# BIRDS_X_APRS_v2_7.net
KiCad netlist of a schematic drawn in EAGLE
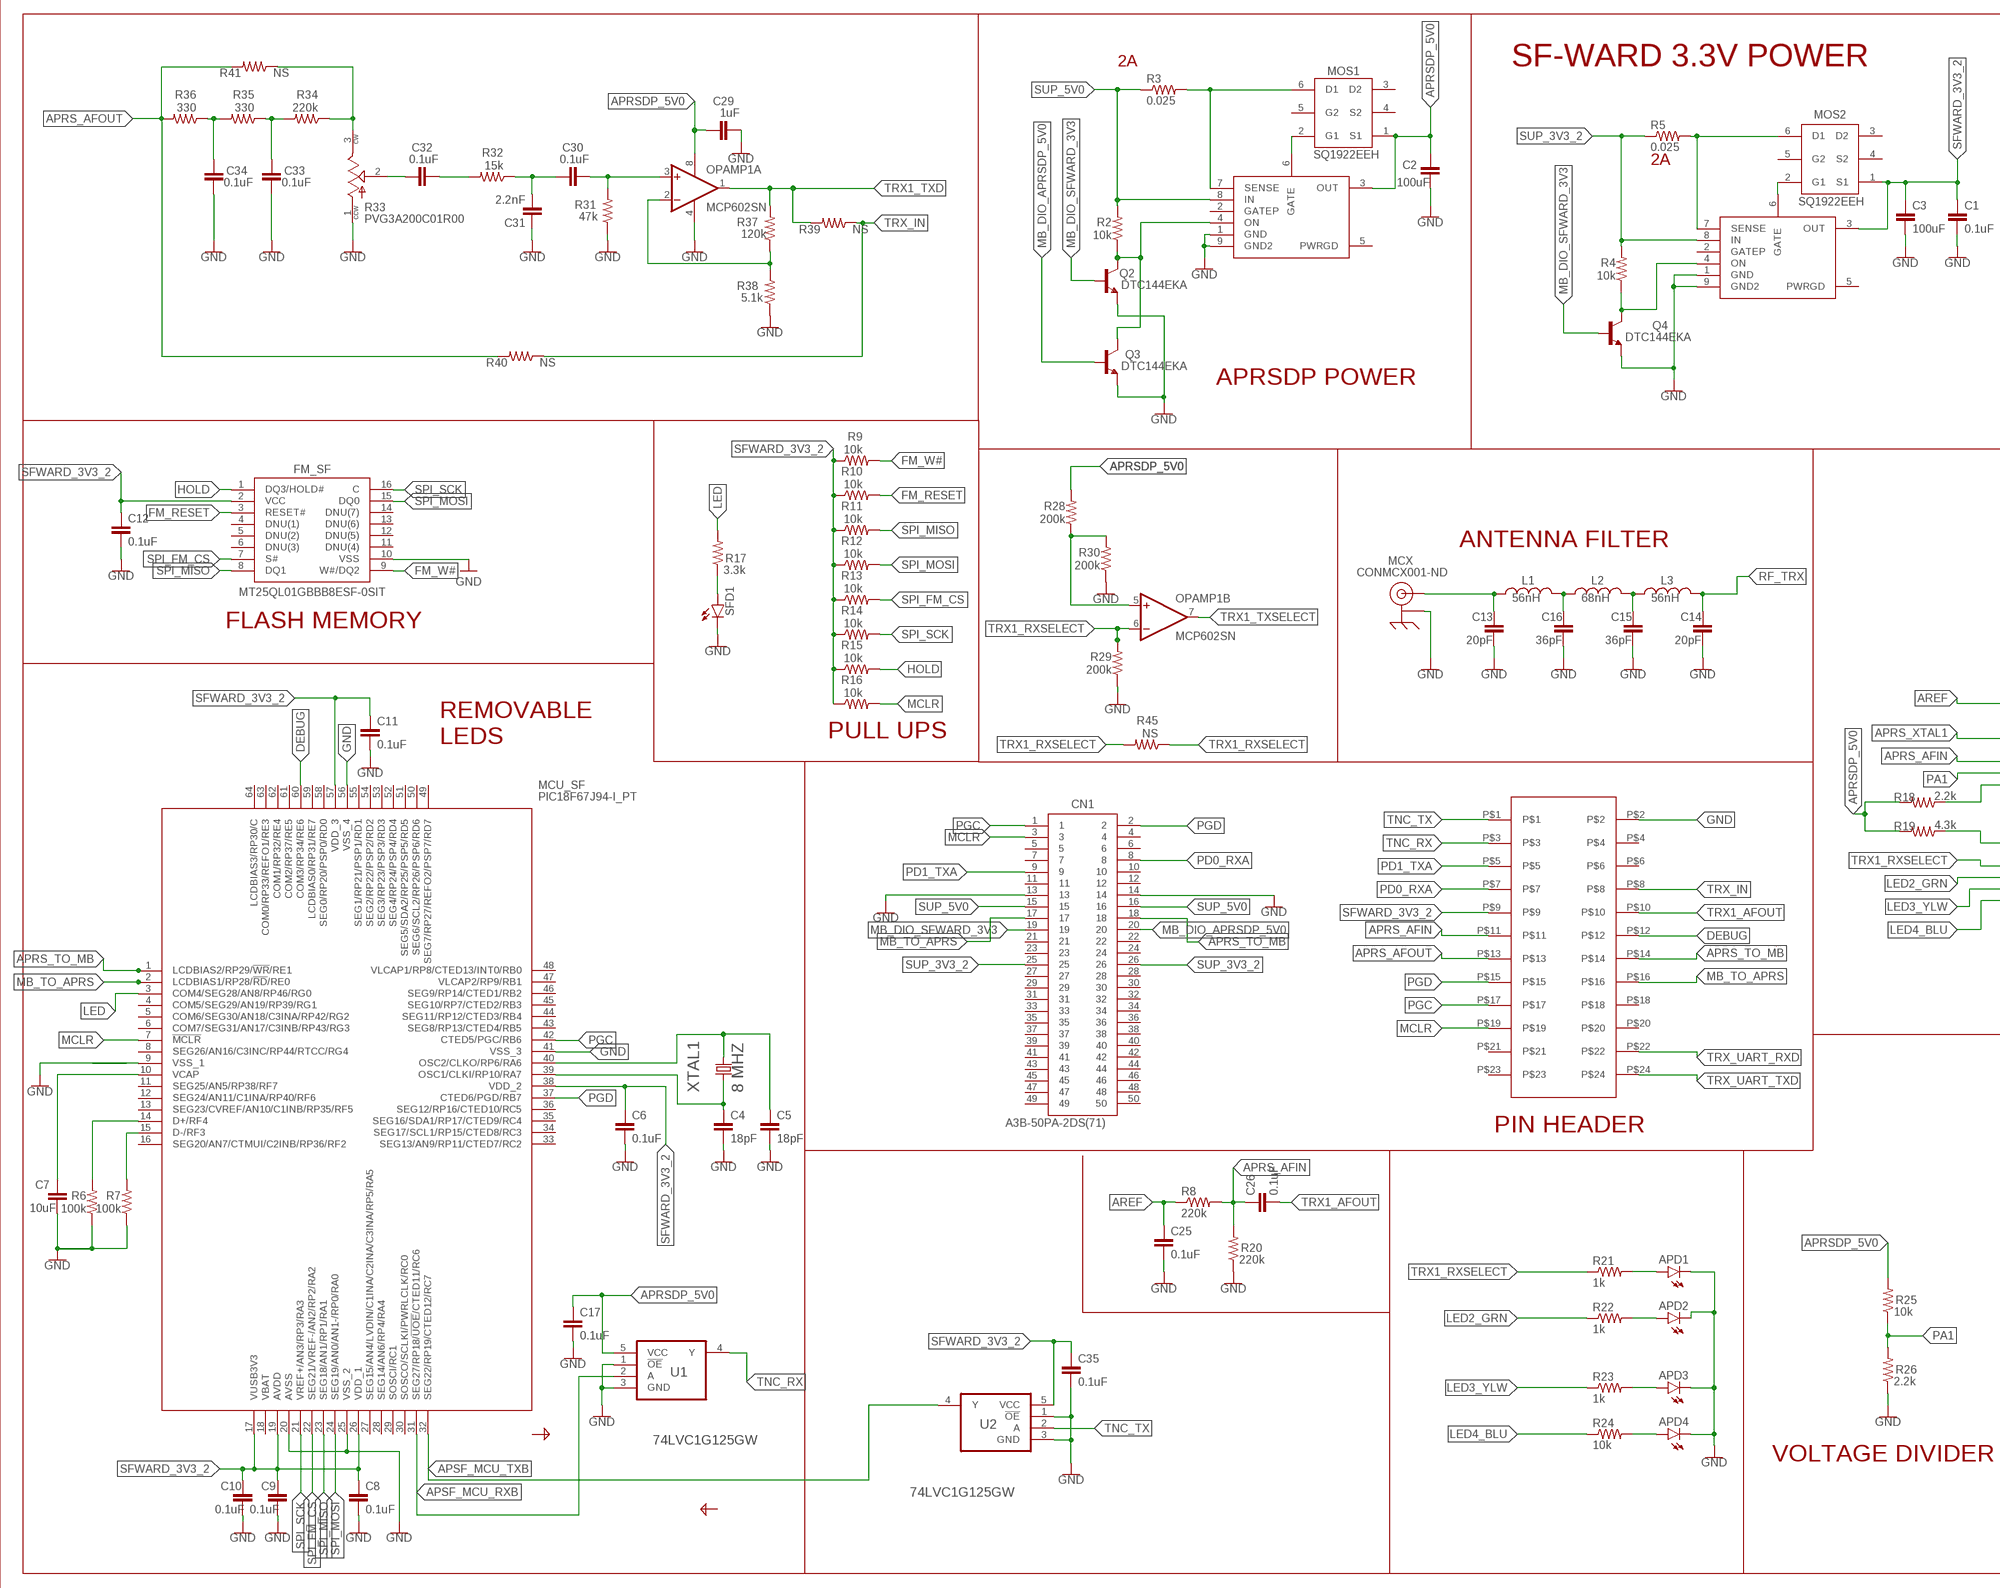
[diagram p0: schematic, sheet 1, part 1 of 2]
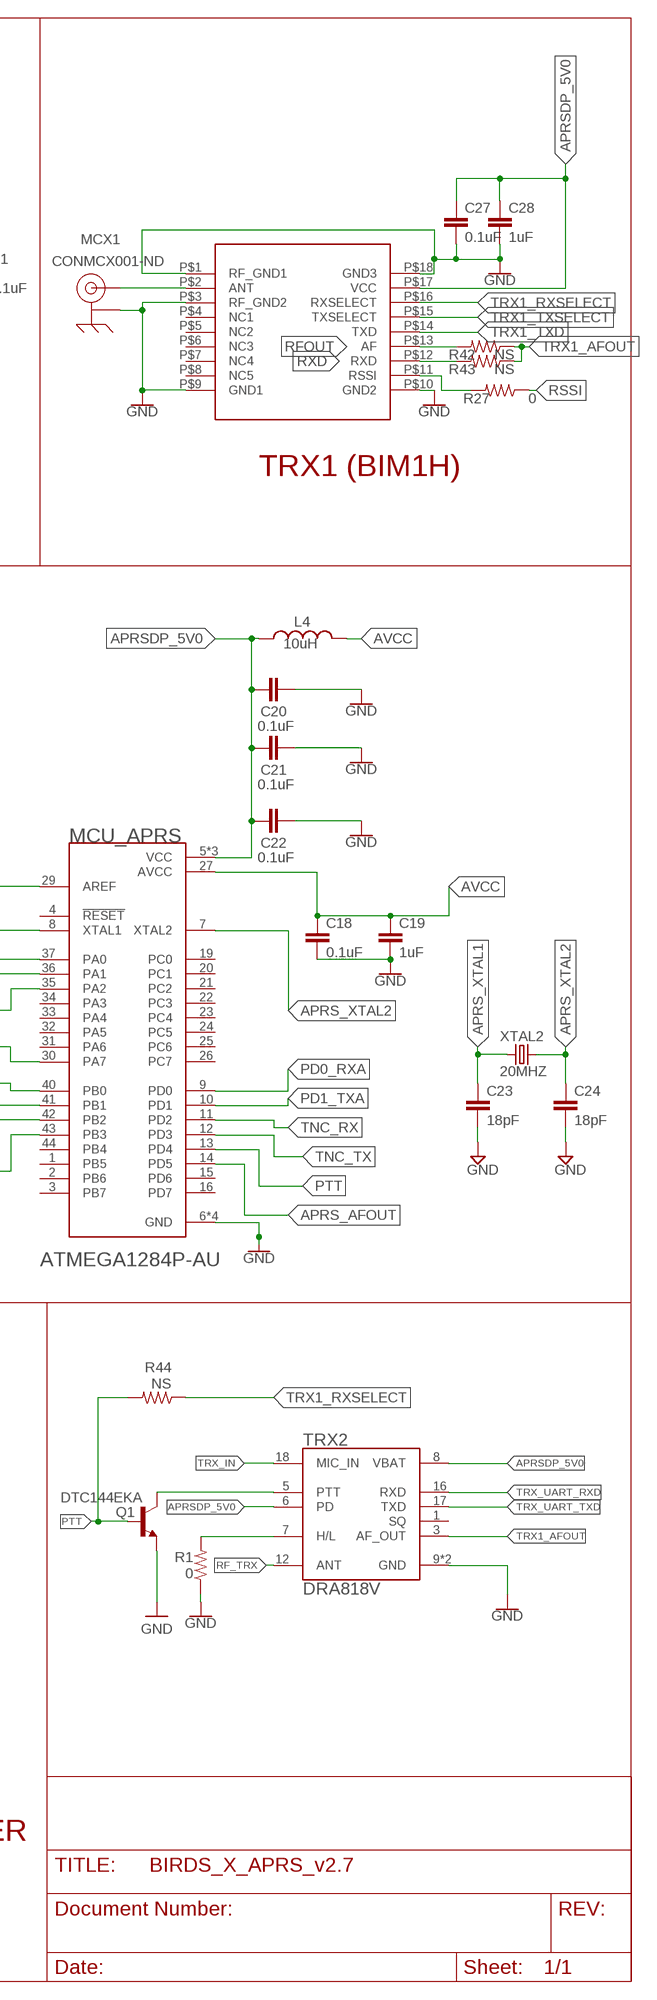
[diagram p1: schematic, sheet 1, part 2 of 2]

(export (version "E")
  (design (tool "Eeschema 10.0.6"))
  (components
    (comp (ref "APD1")
      (value "LEDSML0603")
      (footprint "eagle-import:SML0603")
      (libsource (lib "eagle-import") (part "LEDSML0603"))
    )
    (comp (ref "APD2")
      (value "LEDSML0603")
      (footprint "eagle-import:SML0603")
      (libsource (lib "eagle-import") (part "LEDSML0603"))
    )
    (comp (ref "APD3")
      (value "LEDSML0603")
      (footprint "eagle-import:SML0603")
      (libsource (lib "eagle-import") (part "LEDSML0603"))
    )
    (comp (ref "APD4")
      (value "LEDSML0603")
      (footprint "eagle-import:SML0603")
      (libsource (lib "eagle-import") (part "LEDSML0603"))
    )
    (comp (ref "C1")
      (value "0.1uF")
      (footprint "eagle-import:M(1005)_US(0402)")
      (libsource (lib "eagle-import") (part "CAPACITOR"))
    )
    (comp (ref "C2")
      (value "100uF")
      (footprint "eagle-import:M(2012)_US(0805)")
      (libsource (lib "eagle-import") (part "CAPACITOR2012"))
    )
    (comp (ref "C3")
      (value "100uF")
      (footprint "eagle-import:M(2012)_US(0805)")
      (libsource (lib "eagle-import") (part "CAPACITOR2012"))
    )
    (comp (ref "C4")
      (value "18pF")
      (footprint "eagle-import:M(1005)_US(0402)")
      (libsource (lib "eagle-import") (part "CAPACITOR"))
    )
    (comp (ref "C5")
      (value "18pF")
      (footprint "eagle-import:M(1005)_US(0402)")
      (libsource (lib "eagle-import") (part "CAPACITOR"))
    )
    (comp (ref "C6")
      (value "0.1uF")
      (footprint "eagle-import:M(1005)_US(0402)")
      (libsource (lib "eagle-import") (part "CAPACITOR"))
    )
    (comp (ref "C7")
      (value "10uF")
      (footprint "eagle-import:M(1608)_US(0603)")
      (libsource (lib "eagle-import") (part "CAPACITOR1608"))
    )
    (comp (ref "C8")
      (value "0.1uF")
      (footprint "eagle-import:M(1005)_US(0402)")
      (libsource (lib "eagle-import") (part "CAPACITOR"))
    )
    (comp (ref "C9")
      (value "0.1uF")
      (footprint "eagle-import:M(1005)_US(0402)")
      (libsource (lib "eagle-import") (part "CAPACITOR"))
    )
    (comp (ref "C10")
      (value "0.1uF")
      (footprint "eagle-import:M(1005)_US(0402)")
      (libsource (lib "eagle-import") (part "CAPACITOR"))
    )
    (comp (ref "C11")
      (value "0.1uF")
      (footprint "eagle-import:M(1005)_US(0402)")
      (libsource (lib "eagle-import") (part "CAPACITOR"))
    )
    (comp (ref "C12")
      (value "0.1uF")
      (footprint "eagle-import:M(1005)_US(0402)")
      (libsource (lib "eagle-import") (part "CAPACITOR"))
    )
    (comp (ref "C13")
      (value "20pF")
      (footprint "eagle-import:M(1608)_US(0603)")
      (libsource (lib "eagle-import") (part "CAPACITOR1608"))
    )
    (comp (ref "C14")
      (value "20pF")
      (footprint "eagle-import:M(1608)_US(0603)")
      (libsource (lib "eagle-import") (part "CAPACITOR1608"))
    )
    (comp (ref "C15")
      (value "36pF")
      (footprint "eagle-import:M(1608)_US(0603)")
      (libsource (lib "eagle-import") (part "CAPACITOR1608"))
    )
    (comp (ref "C16")
      (value "36pF")
      (footprint "eagle-import:M(1608)_US(0603)")
      (libsource (lib "eagle-import") (part "CAPACITOR1608"))
    )
    (comp (ref "C17")
      (value "0.1uF")
      (footprint "eagle-import:M(1005)_US(0402)")
      (libsource (lib "eagle-import") (part "CAPACITOR"))
    )
    (comp (ref "C18")
      (value "0.1uF")
      (footprint "eagle-import:M(1005)_US(0402)")
      (libsource (lib "eagle-import") (part "CAPACITOR"))
    )
    (comp (ref "C19")
      (value "1uF")
      (footprint "eagle-import:M(1005)_US(0402)")
      (libsource (lib "eagle-import") (part "CAPACITOR"))
    )
    (comp (ref "C20")
      (value "0.1uF")
      (footprint "eagle-import:M(1005)_US(0402)")
      (libsource (lib "eagle-import") (part "CAPACITOR"))
    )
    (comp (ref "C21")
      (value "0.1uF")
      (footprint "eagle-import:M(1005)_US(0402)")
      (libsource (lib "eagle-import") (part "CAPACITOR"))
    )
    (comp (ref "C22")
      (value "0.1uF")
      (footprint "eagle-import:M(1005)_US(0402)")
      (libsource (lib "eagle-import") (part "CAPACITOR"))
    )
    (comp (ref "C23")
      (value "18pF")
      (footprint "eagle-import:M(1005)_US(0402)")
      (libsource (lib "eagle-import") (part "CAPACITOR"))
    )
    (comp (ref "C24")
      (value "18pF")
      (footprint "eagle-import:M(1005)_US(0402)")
      (libsource (lib "eagle-import") (part "CAPACITOR"))
    )
    (comp (ref "C25")
      (value "0.1uF")
      (footprint "eagle-import:M(1005)_US(0402)")
      (libsource (lib "eagle-import") (part "CAPACITOR"))
    )
    (comp (ref "C26")
      (value "0.1uF")
      (footprint "eagle-import:M(1005)_US(0402)")
      (libsource (lib "eagle-import") (part "CAPACITOR"))
    )
    (comp (ref "C27")
      (value "0.1uF")
      (footprint "eagle-import:M(1005)_US(0402)")
      (libsource (lib "eagle-import") (part "CAPACITOR"))
    )
    (comp (ref "C28")
      (value "1uF")
      (footprint "eagle-import:M(1005)_US(0402)")
      (libsource (lib "eagle-import") (part "CAPACITOR"))
    )
    (comp (ref "C29")
      (value "1uF")
      (footprint "eagle-import:M(1005)_US(0402)")
      (libsource (lib "eagle-import") (part "CAPACITOR"))
    )
    (comp (ref "C30")
      (value "0.1uF")
      (footprint "eagle-import:M(1005)_US(0402)")
      (libsource (lib "eagle-import") (part "CAPACITOR"))
    )
    (comp (ref "C31")
      (value "2.2nF")
      (footprint "eagle-import:M(1005)_US(0402)")
      (libsource (lib "eagle-import") (part "CAPACITOR"))
    )
    (comp (ref "C32")
      (value "0.1uF")
      (footprint "eagle-import:M(1005)_US(0402)")
      (libsource (lib "eagle-import") (part "CAPACITOR"))
    )
    (comp (ref "C33")
      (value "0.1uF")
      (footprint "eagle-import:M(1005)_US(0402)")
      (libsource (lib "eagle-import") (part "CAPACITOR"))
    )
    (comp (ref "C34")
      (value "0.1uF")
      (footprint "eagle-import:M(1005)_US(0402)")
      (libsource (lib "eagle-import") (part "CAPACITOR"))
    )
    (comp (ref "C35")
      (value "0.1uF")
      (footprint "eagle-import:M(1005)_US(0402)")
      (libsource (lib "eagle-import") (part "CAPACITOR"))
    )
    (comp (ref "CN1")
      (value "A3B-50PA-2DS(71)")
      (footprint "eagle-import:A3B-50PA-2DS(71)")
      (libsource (lib "eagle-import") (part "A3B-50PA-2DS(71)"))
    )
    (comp (ref "FM_SF")
      (value "MT25QL01GBBB8ESF-0SIT")
      (footprint "eagle-import:SOIC127P1032X265-16N")
      (libsource (lib "eagle-import") (part "MT25QL01GBBB8ESF-0SIT"))
    )
    (comp (ref "JP1")
      (value "RAB_ACCESS")
      (footprint "eagle-import:RAB_ACCESS")
      (libsource (lib "eagle-import") (part "RAB_ACCESS"))
    )
    (comp (ref "L1")
      (value "56nH")
      (footprint "eagle-import:M(2012)_US(0805)")
      (libsource (lib "eagle-import") (part "INDUCTOR2012"))
    )
    (comp (ref "L2")
      (value "68nH")
      (footprint "eagle-import:M(2012)_US(0805)")
      (libsource (lib "eagle-import") (part "INDUCTOR2012"))
    )
    (comp (ref "L3")
      (value "56nH")
      (footprint "eagle-import:M(2012)_US(0805)")
      (libsource (lib "eagle-import") (part "INDUCTOR2012"))
    )
    (comp (ref "L4")
      (value "10uH")
      (footprint "eagle-import:M(2012)_US(0805)")
      (libsource (lib "eagle-import") (part "INDUCTOR2012"))
    )
    (comp (ref "MCU_APRS")
      (value "ATMEGA1284P-AU")
      (footprint "eagle-import:QFP80P1200X1200X120-44N")
      (fields (field (name "MF") "Microchip"))
      (libsource (lib "eagle-import") (part "ATMEGA1284P-AU"))
    )
    (comp (ref "MCU_SF")
      (value "PIC18F67J94-I_PT")
      (footprint "eagle-import:QFP50P1200X1200X120-64N")
      (fields
        (field (name "MANUFACTURER_PART_NUMBER") "PIC18F67J94-I/PT")
        (field (name "MOUSER_PART_NUMBER") "579-PIC18F67J94-I/PT")
        (field (name "RS_PART_NUMBER") "1652172")
      )
      (libsource (lib "eagle-import") (part "PIC18F67J94-I_PT"))
    )
    (comp (ref "MCX")
      (value "CONMCX001-ND")
      (footprint "eagle-import:CONMCX001-ND")
      (libsource (lib "eagle-import") (part "CONMCX001-ND"))
    )
    (comp (ref "MCX1")
      (value "CONMCX001-ND")
      (footprint "eagle-import:CONMCX001-ND")
      (libsource (lib "eagle-import") (part "CONMCX001-ND"))
    )
    (comp (ref "MOS1")
      (value "SQ1922EEH")
      (footprint "eagle-import:SOT65P210X110-6N")
      (libsource (lib "eagle-import") (part "SQ1922EEH"))
    )
    (comp (ref "MOS2")
      (value "SQ1922EEH")
      (footprint "eagle-import:SOT65P210X110-6N")
      (libsource (lib "eagle-import") (part "SQ1922EEH"))
    )
    (comp (ref "OCP1")
      (value "BIRDS5_LTC4361")
      (footprint "eagle-import:BIRDS5_LTC4361")
      (libsource (lib "eagle-import") (part "BIRDS5_LTC4361"))
    )
    (comp (ref "OCP2")
      (value "BIRDS5_LTC4361")
      (footprint "eagle-import:BIRDS5_LTC4361")
      (libsource (lib "eagle-import") (part "BIRDS5_LTC4361"))
    )
    (comp (ref "OPAMP1")
      (value "MCP602SN")
      (footprint "eagle-import:SO08")
      (libsource (lib "eagle-import") (part "MCP602SN"))
    )
    (comp (ref "Q1")
      (value "DTC144EKA")
      (footprint "eagle-import:SOT346-R")
      (libsource (lib "eagle-import") (part "DTC144EKA"))
    )
    (comp (ref "Q2")
      (value "DTC144EKA")
      (footprint "eagle-import:SOT346-R")
      (libsource (lib "eagle-import") (part "DTC144EKA"))
    )
    (comp (ref "Q3")
      (value "DTC144EKA")
      (footprint "eagle-import:SOT346-R")
      (libsource (lib "eagle-import") (part "DTC144EKA"))
    )
    (comp (ref "Q4")
      (value "DTC144EKA")
      (footprint "eagle-import:SOT346-R")
      (libsource (lib "eagle-import") (part "DTC144EKA"))
    )
    (comp (ref "R1")
      (value "0")
      (footprint "eagle-import:M(1005)_US(0402)")
      (libsource (lib "eagle-import") (part "RESISTOR"))
    )
    (comp (ref "R2")
      (value "10k")
      (footprint "eagle-import:M(1005)_US(0402)")
      (libsource (lib "eagle-import") (part "RESISTOR"))
    )
    (comp (ref "R3")
      (value "0.025")
      (footprint "eagle-import:M(2012)_US(0805)")
      (libsource (lib "eagle-import") (part "RESISTOR2012"))
    )
    (comp (ref "R4")
      (value "10k")
      (footprint "eagle-import:M(1005)_US(0402)")
      (libsource (lib "eagle-import") (part "RESISTOR"))
    )
    (comp (ref "R5")
      (value "0.025")
      (footprint "eagle-import:M(2012)_US(0805)")
      (libsource (lib "eagle-import") (part "RESISTOR2012"))
    )
    (comp (ref "R6")
      (value "100k")
      (footprint "eagle-import:M(1005)_US(0402)")
      (libsource (lib "eagle-import") (part "RESISTOR"))
    )
    (comp (ref "R7")
      (value "100k")
      (footprint "eagle-import:M(1005)_US(0402)")
      (libsource (lib "eagle-import") (part "RESISTOR"))
    )
    (comp (ref "R8")
      (value "220k")
      (footprint "eagle-import:M(1608)_US(0603)")
      (libsource (lib "eagle-import") (part "RESISTOR1608"))
    )
    (comp (ref "R9")
      (value "10k")
      (footprint "eagle-import:M(1005)_US(0402)")
      (libsource (lib "eagle-import") (part "RESISTOR"))
    )
    (comp (ref "R10")
      (value "10k")
      (footprint "eagle-import:M(1005)_US(0402)")
      (libsource (lib "eagle-import") (part "RESISTOR"))
    )
    (comp (ref "R11")
      (value "10k")
      (footprint "eagle-import:M(1005)_US(0402)")
      (libsource (lib "eagle-import") (part "RESISTOR"))
    )
    (comp (ref "R12")
      (value "10k")
      (footprint "eagle-import:M(1005)_US(0402)")
      (libsource (lib "eagle-import") (part "RESISTOR"))
    )
    (comp (ref "R13")
      (value "10k")
      (footprint "eagle-import:M(1005)_US(0402)")
      (libsource (lib "eagle-import") (part "RESISTOR"))
    )
    (comp (ref "R14")
      (value "10k")
      (footprint "eagle-import:M(1005)_US(0402)")
      (libsource (lib "eagle-import") (part "RESISTOR"))
    )
    (comp (ref "R15")
      (value "10k")
      (footprint "eagle-import:M(1005)_US(0402)")
      (libsource (lib "eagle-import") (part "RESISTOR"))
    )
    (comp (ref "R16")
      (value "10k")
      (footprint "eagle-import:M(1005)_US(0402)")
      (libsource (lib "eagle-import") (part "RESISTOR"))
    )
    (comp (ref "R17")
      (value "3.3k")
      (footprint "eagle-import:M(1608)_US(0603)")
      (libsource (lib "eagle-import") (part "RESISTOR1608"))
    )
    (comp (ref "R18")
      (value "2.2k")
      (footprint "eagle-import:M(1005)_US(0402)")
      (libsource (lib "eagle-import") (part "RESISTOR"))
    )
    (comp (ref "R19")
      (value "4.3k")
      (footprint "eagle-import:M(1005)_US(0402)")
      (libsource (lib "eagle-import") (part "RESISTOR"))
    )
    (comp (ref "R20")
      (value "220k")
      (footprint "eagle-import:M(1608)_US(0603)")
      (libsource (lib "eagle-import") (part "RESISTOR1608"))
    )
    (comp (ref "R21")
      (value "1k")
      (footprint "eagle-import:M(1608)_US(0603)")
      (libsource (lib "eagle-import") (part "RESISTOR1608"))
    )
    (comp (ref "R22")
      (value "1k")
      (footprint "eagle-import:M(1608)_US(0603)")
      (libsource (lib "eagle-import") (part "RESISTOR1608"))
    )
    (comp (ref "R23")
      (value "1k")
      (footprint "eagle-import:M(1608)_US(0603)")
      (libsource (lib "eagle-import") (part "RESISTOR1608"))
    )
    (comp (ref "R24")
      (value "10k")
      (footprint "eagle-import:M(1608)_US(0603)")
      (libsource (lib "eagle-import") (part "RESISTOR1608"))
    )
    (comp (ref "R25")
      (value "10k")
      (footprint "eagle-import:M(1608)_US(0603)")
      (libsource (lib "eagle-import") (part "RESISTOR1608"))
    )
    (comp (ref "R26")
      (value "2.2k")
      (footprint "eagle-import:M(1608)_US(0603)")
      (libsource (lib "eagle-import") (part "RESISTOR1608"))
    )
    (comp (ref "R27")
      (value "0")
      (footprint "eagle-import:M(1608)_US(0603)")
      (libsource (lib "eagle-import") (part "RESISTOR1608"))
    )
    (comp (ref "R28")
      (value "200k")
      (footprint "eagle-import:M(1005)_US(0402)")
      (libsource (lib "eagle-import") (part "RESISTOR"))
    )
    (comp (ref "R29")
      (value "200k")
      (footprint "eagle-import:M(1005)_US(0402)")
      (libsource (lib "eagle-import") (part "RESISTOR"))
    )
    (comp (ref "R30")
      (value "200k")
      (footprint "eagle-import:M(1005)_US(0402)")
      (libsource (lib "eagle-import") (part "RESISTOR"))
    )
    (comp (ref "R31")
      (value "47k")
      (footprint "eagle-import:M(1608)_US(0603)")
      (libsource (lib "eagle-import") (part "RESISTOR1608"))
    )
    (comp (ref "R32")
      (value "15k")
      (footprint "eagle-import:M(1608)_US(0603)")
      (libsource (lib "eagle-import") (part "RESISTOR1608"))
    )
    (comp (ref "R33")
      (value "PVG3A200C01R00")
      (footprint "eagle-import:TRIM_PVG3A200C01R00")
      (fields (field (name "DIGI-KEY_PART_NUMBER") "490-2647-1-ND") (field (name "MF") "Bourns"))
      (libsource (lib "eagle-import") (part "PVG3A200C01R00"))
    )
    (comp (ref "R34")
      (value "220k")
      (footprint "eagle-import:M(1608)_US(0603)")
      (libsource (lib "eagle-import") (part "RESISTOR1608"))
    )
    (comp (ref "R35")
      (value "330")
      (footprint "eagle-import:M(1608)_US(0603)")
      (libsource (lib "eagle-import") (part "RESISTOR1608"))
    )
    (comp (ref "R36")
      (value "330")
      (footprint "eagle-import:M(1608)_US(0603)")
      (libsource (lib "eagle-import") (part "RESISTOR1608"))
    )
    (comp (ref "R37")
      (value "120k")
      (footprint "eagle-import:M(1608)_US(0603)")
      (libsource (lib "eagle-import") (part "RESISTOR1608"))
    )
    (comp (ref "R38")
      (value "5.1k")
      (footprint "eagle-import:M(1608)_US(0603)")
      (libsource (lib "eagle-import") (part "RESISTOR1608"))
    )
    (comp (ref "R39")
      (value "NS")
      (footprint "eagle-import:M(1608)_US(0603)")
      (libsource (lib "eagle-import") (part "RESISTOR1608"))
    )
    (comp (ref "R40")
      (value "NS")
      (footprint "eagle-import:M(1608)_US(0603)")
      (libsource (lib "eagle-import") (part "RESISTOR1608"))
    )
    (comp (ref "R41")
      (value "NS")
      (footprint "eagle-import:M(1608)_US(0603)")
      (libsource (lib "eagle-import") (part "RESISTOR1608"))
    )
    (comp (ref "R42")
      (value "NS")
      (footprint "eagle-import:M(1608)_US(0603)")
      (libsource (lib "eagle-import") (part "RESISTOR1608"))
    )
    (comp (ref "R43")
      (value "NS")
      (footprint "eagle-import:M(1608)_US(0603)")
      (libsource (lib "eagle-import") (part "RESISTOR1608"))
    )
    (comp (ref "R44")
      (value "NS")
      (footprint "eagle-import:M(1608)_US(0603)")
      (libsource (lib "eagle-import") (part "RESISTOR1608"))
    )
    (comp (ref "R45")
      (value "NS")
      (footprint "eagle-import:M(1608)_US(0603)")
      (libsource (lib "eagle-import") (part "RESISTOR1608"))
    )
    (comp (ref "SFD1")
      (value "LEDCHIPLED_0603")
      (footprint "eagle-import:CHIPLED_0603")
      (libsource (lib "eagle-import") (part "LEDCHIPLED_0603"))
    )
    (comp (ref "TRX1")
      (value "BIM1H")
      (footprint "eagle-import:BIM1H")
      (libsource (lib "eagle-import") (part "BIM1H"))
    )
    (comp (ref "TRX2")
      (value "DRA818V")
      (footprint "eagle-import:DORJI_DRA818V")
      (fields (field (name "MF") "DORJI"))
      (libsource (lib "eagle-import") (part "DRA818V"))
    )
    (comp (ref "U1")
      (value "74LVC1G125GW")
      (footprint "eagle-import:SOT65P210X110-5N")
      (fields (field (name "MF") "NXP Semiconductors"))
      (libsource (lib "eagle-import") (part "74LVC1G125GW"))
    )
    (comp (ref "U2")
      (value "74LVC1G125GW")
      (footprint "eagle-import:SOT65P210X110-5N")
      (fields (field (name "MF") "NXP Semiconductors"))
      (libsource (lib "eagle-import") (part "74LVC1G125GW"))
    )
    (comp (ref "XTAL1")
      (value "8 MHZ")
      (footprint "eagle-import:CRYSTAL_SM49")
      (libsource (lib "eagle-import") (part "CRYSTAL_CRYSTALSM49"))
    )
    (comp (ref "XTAL2")
      (value "20MHZ")
      (footprint "eagle-import:SM49")
      (libsource (lib "eagle-import") (part "CRYSTALSM49"))
    )
  )
  (nets
    (net (code "1") (name "APRSDP_5V0") (class "Default")
      (node (ref "C17") (pin "1") (pinfunction "1_1") (pintype "passive"))
      (node (ref "C2") (pin "1") (pinfunction "1_1") (pintype "passive"))
      (node (ref "C20") (pin "1") (pinfunction "1_1") (pintype "passive"))
      (node (ref "C21") (pin "1") (pinfunction "1_1") (pintype "passive"))
      (node (ref "C22") (pin "1") (pinfunction "1_1") (pintype "passive"))
      (node (ref "C27") (pin "1") (pinfunction "1_1") (pintype "passive"))
      (node (ref "C28") (pin "1") (pinfunction "1_1") (pintype "passive"))
      (node (ref "C29") (pin "1") (pinfunction "1_1") (pintype "passive"))
      (node (ref "L4") (pin "1") (pinfunction "1_1") (pintype "passive"))
      (node (ref "MCU_APRS") (pin "17") (pinfunction "VCC_17") (pintype "power_in"))
      (node (ref "MCU_APRS") (pin "38") (pinfunction "VCC_38") (pintype "power_in"))
      (node (ref "MCU_APRS") (pin "5") (pinfunction "VCC_5") (pintype "power_in"))
      (node (ref "MOS1") (pin "1") (pinfunction "S1_1") (pintype "input"))
      (node (ref "OCP1") (pin "3") (pinfunction "OUT_3") (pintype "bidirectional"))
      (node (ref "OPAMP1") (pin "8") (pinfunction "V+_8") (pintype "power_in"))
      (node (ref "R18") (pin "2") (pinfunction "2_2") (pintype "passive"))
      (node (ref "R19") (pin "2") (pinfunction "2_2") (pintype "passive"))
      (node (ref "R25") (pin "2") (pinfunction "2_2") (pintype "passive"))
      (node (ref "R28") (pin "2") (pinfunction "2_2") (pintype "passive"))
      (node (ref "TRX1") (pin "P$17") (pinfunction "VCC_P$17") (pintype "bidirectional"))
      (node (ref "TRX2") (pin "6") (pinfunction "PD_6") (pintype "input"))
      (node (ref "TRX2") (pin "8") (pinfunction "VBAT_8") (pintype "power_in"))
      (node (ref "U1") (pin "5") (pinfunction "VCC_5") (pintype "power_in"))
    )
    (net (code "2") (name "APRS_AFIN") (class "Default")
      (node (ref "C26") (pin "1") (pinfunction "1_1") (pintype "passive"))
      (node (ref "JP1") (pin "P$11") (pinfunction "P$11_P$11") (pintype "bidirectional"))
      (node (ref "MCU_APRS") (pin "37") (pinfunction "PA0_37") (pintype "bidirectional"))
      (node (ref "R20") (pin "2") (pinfunction "2_2") (pintype "passive"))
      (node (ref "R8") (pin "2") (pinfunction "2_2") (pintype "passive"))
    )
    (net (code "3") (name "APRS_AFOUT") (class "Default")
      (node (ref "JP1") (pin "P$13") (pinfunction "P$13_P$13") (pintype "bidirectional"))
      (node (ref "MCU_APRS") (pin "14") (pinfunction "PD5_14") (pintype "bidirectional"))
      (node (ref "R36") (pin "2") (pinfunction "2_2") (pintype "passive"))
      (node (ref "R40") (pin "2") (pinfunction "2_2") (pintype "passive"))
      (node (ref "R41") (pin "2") (pinfunction "2_2") (pintype "passive"))
    )
    (net (code "4") (name "APRS_TO_MB") (class "Default")
      (node (ref "CN1") (pin "18") (pinfunction "18_18") (pintype "bidirectional"))
      (node (ref "JP1") (pin "P$14") (pinfunction "P$14_P$14") (pintype "bidirectional"))
      (node (ref "MCU_SF") (pin "1") (pinfunction "LCDBIAS2/RP29/~{WR}/RE1_1") (pintype "bidirectional"))
    )
    (net (code "5") (name "APRS_XTAL1") (class "Default")
      (node (ref "C23") (pin "1") (pinfunction "1_1") (pintype "passive"))
      (node (ref "MCU_APRS") (pin "8") (pinfunction "XTAL1_8") (pintype "input"))
      (node (ref "XTAL2") (pin "1") (pinfunction "1_1") (pintype "passive"))
    )
    (net (code "6") (name "APRS_XTAL2") (class "Default")
      (node (ref "C24") (pin "1") (pinfunction "1_1") (pintype "passive"))
      (node (ref "MCU_APRS") (pin "7") (pinfunction "XTAL2_7") (pintype "output"))
      (node (ref "XTAL2") (pin "2") (pinfunction "2_2") (pintype "passive"))
    )
    (net (code "7") (name "APSF_MCU_RXB") (class "Default")
      (node (ref "MCU_SF") (pin "31") (pinfunction "SEG27/RP18/~{UOE}/CTED11/RC6_31") (pintype "bidirectional"))
      (node (ref "U1") (pin "2") (pinfunction "A_2") (pintype "input"))
    )
    (net (code "8") (name "APSF_MCU_TXB") (class "Default")
      (node (ref "MCU_SF") (pin "32") (pinfunction "SEG22/RP19/CTED12/RC7_32") (pintype "bidirectional"))
      (node (ref "U2") (pin "4") (pinfunction "Y_4") (pintype "output"))
    )
    (net (code "9") (name "AREF") (class "Default")
      (node (ref "C25") (pin "1") (pinfunction "1_1") (pintype "passive"))
      (node (ref "MCU_APRS") (pin "29") (pinfunction "AREF_29") (pintype "input"))
      (node (ref "R8") (pin "1") (pinfunction "1_1") (pintype "passive"))
    )
    (net (code "10") (name "AVCC") (class "Default")
      (node (ref "C18") (pin "1") (pinfunction "1_1") (pintype "passive"))
      (node (ref "C19") (pin "1") (pinfunction "1_1") (pintype "passive"))
      (node (ref "L4") (pin "2") (pinfunction "2_2") (pintype "passive"))
      (node (ref "MCU_APRS") (pin "27") (pinfunction "AVCC_27") (pintype "power_in"))
    )
    (net (code "11") (name "DEBUG") (class "Default")
      (node (ref "JP1") (pin "P$12") (pinfunction "P$12_P$12") (pintype "bidirectional"))
      (node (ref "MCU_SF") (pin "60") (pinfunction "COM3/RP34/RE6_60") (pintype "bidirectional"))
    )
    (net (code "12") (name "FM_RESET") (class "Default")
      (node (ref "FM_SF") (pin "3") (pinfunction "RESET#_3") (pintype "input"))
      (node (ref "R10") (pin "2") (pinfunction "2_2") (pintype "passive"))
    )
    (net (code "13") (name "FM_W#") (class "Default")
      (node (ref "FM_SF") (pin "9") (pinfunction "W#/DQ2_9") (pintype "input"))
      (node (ref "R9") (pin "2") (pinfunction "2_2") (pintype "passive"))
    )
    (net (code "14") (name "GND") (class "Default")
      (node (ref "APD1") (pin "C") (pinfunction "C_C") (pintype "passive"))
      (node (ref "APD2") (pin "C") (pinfunction "C_C") (pintype "passive"))
      (node (ref "APD3") (pin "C") (pinfunction "C_C") (pintype "passive"))
      (node (ref "APD4") (pin "C") (pinfunction "C_C") (pintype "passive"))
      (node (ref "C1") (pin "2") (pinfunction "2_2") (pintype "passive"))
      (node (ref "C10") (pin "2") (pinfunction "2_2") (pintype "passive"))
      (node (ref "C11") (pin "2") (pinfunction "2_2") (pintype "passive"))
      (node (ref "C12") (pin "2") (pinfunction "2_2") (pintype "passive"))
      (node (ref "C13") (pin "2") (pinfunction "2_2") (pintype "passive"))
      (node (ref "C14") (pin "2") (pinfunction "2_2") (pintype "passive"))
      (node (ref "C15") (pin "2") (pinfunction "2_2") (pintype "passive"))
      (node (ref "C16") (pin "2") (pinfunction "2_2") (pintype "passive"))
      (node (ref "C17") (pin "2") (pinfunction "2_2") (pintype "passive"))
      (node (ref "C18") (pin "2") (pinfunction "2_2") (pintype "passive"))
      (node (ref "C19") (pin "2") (pinfunction "2_2") (pintype "passive"))
      (node (ref "C2") (pin "2") (pinfunction "2_2") (pintype "passive"))
      (node (ref "C20") (pin "2") (pinfunction "2_2") (pintype "passive"))
      (node (ref "C21") (pin "2") (pinfunction "2_2") (pintype "passive"))
      (node (ref "C22") (pin "2") (pinfunction "2_2") (pintype "passive"))
      (node (ref "C23") (pin "2") (pinfunction "2_2") (pintype "passive"))
      (node (ref "C24") (pin "2") (pinfunction "2_2") (pintype "passive"))
      (node (ref "C25") (pin "2") (pinfunction "2_2") (pintype "passive"))
      (node (ref "C27") (pin "2") (pinfunction "2_2") (pintype "passive"))
      (node (ref "C28") (pin "2") (pinfunction "2_2") (pintype "passive"))
      (node (ref "C29") (pin "2") (pinfunction "2_2") (pintype "passive"))
      (node (ref "C3") (pin "2") (pinfunction "2_2") (pintype "passive"))
      (node (ref "C31") (pin "1") (pinfunction "1_1") (pintype "passive"))
      (node (ref "C33") (pin "2") (pinfunction "2_2") (pintype "passive"))
      (node (ref "C34") (pin "2") (pinfunction "2_2") (pintype "passive"))
      (node (ref "C35") (pin "2") (pinfunction "2_2") (pintype "passive"))
      (node (ref "C4") (pin "2") (pinfunction "2_2") (pintype "passive"))
      (node (ref "C5") (pin "2") (pinfunction "2_2") (pintype "passive"))
      (node (ref "C6") (pin "2") (pinfunction "2_2") (pintype "passive"))
      (node (ref "C7") (pin "2") (pinfunction "2_2") (pintype "passive"))
      (node (ref "C8") (pin "2") (pinfunction "2_2") (pintype "passive"))
      (node (ref "C9") (pin "2") (pinfunction "2_2") (pintype "passive"))
      (node (ref "CN1") (pin "13") (pinfunction "13_13") (pintype "bidirectional"))
      (node (ref "CN1") (pin "14") (pinfunction "14_14") (pintype "bidirectional"))
      (node (ref "FM_SF") (pin "10") (pinfunction "VSS_10") (pintype "input"))
      (node (ref "JP1") (pin "P$2") (pinfunction "P$2_P$2") (pintype "bidirectional"))
      (node (ref "MCU_APRS") (pin "18") (pinfunction "GND_18") (pintype "power_in"))
      (node (ref "MCU_APRS") (pin "28") (pinfunction "GND_28") (pintype "power_in"))
      (node (ref "MCU_APRS") (pin "39") (pinfunction "GND_39") (pintype "power_in"))
      (node (ref "MCU_APRS") (pin "6") (pinfunction "GND_6") (pintype "power_in"))
      (node (ref "MCU_SF") (pin "20") (pinfunction "AVSS_20") (pintype "bidirectional"))
      (node (ref "MCU_SF") (pin "25") (pinfunction "VSS_2_25") (pintype "bidirectional"))
      (node (ref "MCU_SF") (pin "41") (pinfunction "VSS_3_41") (pintype "bidirectional"))
      (node (ref "MCU_SF") (pin "56") (pinfunction "VSS_4_56") (pintype "bidirectional"))
      (node (ref "MCU_SF") (pin "9") (pinfunction "VSS_1_9") (pintype "bidirectional"))
      (node (ref "MCX") (pin "2") (pinfunction "2_2") (pintype "bidirectional"))
      (node (ref "MCX") (pin "3") (pinfunction "2_3") (pintype "bidirectional"))
      (node (ref "MCX") (pin "4") (pinfunction "2_4") (pintype "bidirectional"))
      (node (ref "MCX") (pin "5") (pinfunction "2_5") (pintype "bidirectional"))
      (node (ref "MCX1") (pin "2") (pinfunction "2_2") (pintype "bidirectional"))
      (node (ref "MCX1") (pin "3") (pinfunction "2_3") (pintype "bidirectional"))
      (node (ref "MCX1") (pin "4") (pinfunction "2_4") (pintype "bidirectional"))
      (node (ref "MCX1") (pin "5") (pinfunction "2_5") (pintype "bidirectional"))
      (node (ref "OCP1") (pin "1") (pinfunction "GND_1") (pintype "bidirectional"))
      (node (ref "OCP1") (pin "9") (pinfunction "GND2_9") (pintype "bidirectional"))
      (node (ref "OCP2") (pin "1") (pinfunction "GND_1") (pintype "bidirectional"))
      (node (ref "OCP2") (pin "9") (pinfunction "GND2_9") (pintype "bidirectional"))
      (node (ref "OPAMP1") (pin "4") (pinfunction "V-_4") (pintype "power_in"))
      (node (ref "Q1") (pin "1") (pinfunction "E_1") (pintype "passive"))
      (node (ref "Q2") (pin "1") (pinfunction "E_1") (pintype "passive"))
      (node (ref "Q3") (pin "1") (pinfunction "E_1") (pintype "passive"))
      (node (ref "Q4") (pin "1") (pinfunction "E_1") (pintype "passive"))
      (node (ref "R1") (pin "1") (pinfunction "1_1") (pintype "passive"))
      (node (ref "R20") (pin "1") (pinfunction "1_1") (pintype "passive"))
      (node (ref "R26") (pin "1") (pinfunction "1_1") (pintype "passive"))
      (node (ref "R30") (pin "1") (pinfunction "1_1") (pintype "passive"))
      (node (ref "R31") (pin "1") (pinfunction "1_1") (pintype "passive"))
      (node (ref "R33") (pin "1") (pinfunction "CCW_1") (pintype "passive"))
      (node (ref "R38") (pin "1") (pinfunction "1_1") (pintype "passive"))
      (node (ref "TRX1") (pin "P$1") (pinfunction "RF_GND1_P$1") (pintype "bidirectional"))
      (node (ref "TRX1") (pin "P$10") (pinfunction "GND2_P$10") (pintype "bidirectional"))
      (node (ref "TRX1") (pin "P$18") (pinfunction "GND3_P$18") (pintype "bidirectional"))
      (node (ref "TRX1") (pin "P$3") (pinfunction "RF_GND2_P$3") (pintype "bidirectional"))
      (node (ref "TRX1") (pin "P$9") (pinfunction "GND1_P$9") (pintype "bidirectional"))
      (node (ref "TRX2") (pin "10") (pinfunction "GND_10") (pintype "power_in"))
      (node (ref "TRX2") (pin "9") (pinfunction "GND_9") (pintype "power_in"))
      (node (ref "U1") (pin "1") (pinfunction "~{OE}_1") (pintype "input"))
      (node (ref "U1") (pin "3") (pinfunction "GND_3") (pintype "passive"))
      (node (ref "U2") (pin "1") (pinfunction "~{OE}_1") (pintype "input"))
      (node (ref "U2") (pin "3") (pinfunction "GND_3") (pintype "passive"))
    )
    (net (code "15") (name "HOLD") (class "Default")
      (node (ref "FM_SF") (pin "1") (pinfunction "DQ3/HOLD#_1") (pintype "input"))
      (node (ref "R15") (pin "2") (pinfunction "2_2") (pintype "passive"))
    )
    (net (code "16") (name "LED") (class "Default")
      (node (ref "MCU_SF") (pin "3") (pinfunction "COM4/SEG28/AN8/RP46/RG0_3") (pintype "bidirectional"))
      (node (ref "R17") (pin "2") (pinfunction "2_2") (pintype "passive"))
    )
    (net (code "17") (name "LED2_GRN") (class "Default")
      (node (ref "MCU_APRS") (pin "41") (pinfunction "PB1_41") (pintype "bidirectional"))
      (node (ref "R22") (pin "1") (pinfunction "1_1") (pintype "passive"))
    )
    (net (code "18") (name "LED3_YLW") (class "Default")
      (node (ref "MCU_APRS") (pin "42") (pinfunction "PB2_42") (pintype "bidirectional"))
      (node (ref "R23") (pin "1") (pinfunction "1_1") (pintype "passive"))
    )
    (net (code "19") (name "LED4_BLU") (class "Default")
      (node (ref "MCU_APRS") (pin "43") (pinfunction "PB3_43") (pintype "bidirectional"))
      (node (ref "R24") (pin "1") (pinfunction "1_1") (pintype "passive"))
    )
    (net (code "20") (name "MB_DIO_APRSDP_5V0") (class "Default")
      (node (ref "CN1") (pin "20") (pinfunction "20_20") (pintype "bidirectional"))
      (node (ref "Q3") (pin "2") (pinfunction "B_2") (pintype "passive"))
    )
    (net (code "21") (name "MB_DIO_SFWARD_3V3") (class "Default")
      (node (ref "CN1") (pin "19") (pinfunction "19_19") (pintype "bidirectional"))
      (node (ref "Q2") (pin "2") (pinfunction "B_2") (pintype "passive"))
      (node (ref "Q4") (pin "2") (pinfunction "B_2") (pintype "passive"))
    )
    (net (code "22") (name "MB_TO_APRS") (class "Default")
      (node (ref "CN1") (pin "17") (pinfunction "17_17") (pintype "bidirectional"))
      (node (ref "JP1") (pin "P$16") (pinfunction "P$16_P$16") (pintype "bidirectional"))
      (node (ref "MCU_SF") (pin "2") (pinfunction "LCDBIAS1/RP28/~{RD}/RE0_2") (pintype "bidirectional"))
    )
    (net (code "23") (name "MCLR") (class "Default")
      (node (ref "CN1") (pin "3") (pinfunction "3_3") (pintype "bidirectional"))
      (node (ref "JP1") (pin "P$19") (pinfunction "P$19_P$19") (pintype "bidirectional"))
      (node (ref "MCU_SF") (pin "7") (pinfunction "~{MCLR}_7") (pintype "bidirectional"))
      (node (ref "R16") (pin "2") (pinfunction "2_2") (pintype "passive"))
    )
    (net (code "24") (name "Net-(APD1-PadA)") (class "Default")
      (node (ref "APD1") (pin "A") (pinfunction "A_A") (pintype "passive"))
      (node (ref "R21") (pin "2") (pinfunction "2_2") (pintype "passive"))
    )
    (net (code "25") (name "Net-(APD2-PadA)") (class "Default")
      (node (ref "APD2") (pin "A") (pinfunction "A_A") (pintype "passive"))
      (node (ref "R22") (pin "2") (pinfunction "2_2") (pintype "passive"))
    )
    (net (code "26") (name "Net-(APD3-PadA)") (class "Default")
      (node (ref "APD3") (pin "A") (pinfunction "A_A") (pintype "passive"))
      (node (ref "R23") (pin "2") (pinfunction "2_2") (pintype "passive"))
    )
    (net (code "27") (name "Net-(APD4-PadA)") (class "Default")
      (node (ref "APD4") (pin "A") (pinfunction "A_A") (pintype "passive"))
      (node (ref "R24") (pin "2") (pinfunction "2_2") (pintype "passive"))
    )
    (net (code "28") (name "Net-(C13-Pad1)") (class "Default")
      (node (ref "C13") (pin "1") (pinfunction "1_1") (pintype "passive"))
      (node (ref "L1") (pin "1") (pinfunction "1_1") (pintype "passive"))
      (node (ref "MCX") (pin "1") (pinfunction "1_1") (pintype "bidirectional"))
    )
    (net (code "29") (name "Net-(C15-Pad1)") (class "Default")
      (node (ref "C15") (pin "1") (pinfunction "1_1") (pintype "passive"))
      (node (ref "L2") (pin "2") (pinfunction "2_2") (pintype "passive"))
      (node (ref "L3") (pin "1") (pinfunction "1_1") (pintype "passive"))
    )
    (net (code "30") (name "Net-(C16-Pad1)") (class "Default")
      (node (ref "C16") (pin "1") (pinfunction "1_1") (pintype "passive"))
      (node (ref "L1") (pin "2") (pinfunction "2_2") (pintype "passive"))
      (node (ref "L2") (pin "1") (pinfunction "1_1") (pintype "passive"))
    )
    (net (code "31") (name "Net-(C30-Pad1)") (class "Default")
      (node (ref "C30") (pin "1") (pinfunction "1_1") (pintype "passive"))
      (node (ref "C31") (pin "2") (pinfunction "2_2") (pintype "passive"))
      (node (ref "R32") (pin "1") (pinfunction "1_1") (pintype "passive"))
    )
    (net (code "32") (name "Net-(C32-Pad2)") (class "Default")
      (node (ref "C32") (pin "2") (pinfunction "2_2") (pintype "passive"))
      (node (ref "R32") (pin "2") (pinfunction "2_2") (pintype "passive"))
    )
    (net (code "33") (name "Net-(C33-Pad1)") (class "Default")
      (node (ref "C33") (pin "1") (pinfunction "1_1") (pintype "passive"))
      (node (ref "R34") (pin "2") (pinfunction "2_2") (pintype "passive"))
      (node (ref "R35") (pin "1") (pinfunction "1_1") (pintype "passive"))
    )
    (net (code "34") (name "Net-(C34-Pad1)") (class "Default")
      (node (ref "C34") (pin "1") (pinfunction "1_1") (pintype "passive"))
      (node (ref "R35") (pin "2") (pinfunction "2_2") (pintype "passive"))
      (node (ref "R36") (pin "1") (pinfunction "1_1") (pintype "passive"))
    )
    (net (code "35") (name "Net-(MCU_APRS-PA2)") (class "Default")
      (node (ref "MCU_APRS") (pin "35") (pinfunction "PA2_35") (pintype "bidirectional"))
      (node (ref "R18") (pin "1") (pinfunction "1_1") (pintype "passive"))
    )
    (net (code "36") (name "Net-(MCU_APRS-PA7)") (class "Default")
      (node (ref "MCU_APRS") (pin "30") (pinfunction "PA7_30") (pintype "bidirectional"))
      (node (ref "R19") (pin "1") (pinfunction "1_1") (pintype "passive"))
    )
    (net (code "37") (name "Net-(MCU_SF-D+{slash}RF4)") (class "Default")
      (node (ref "MCU_SF") (pin "14") (pinfunction "D+/RF4_14") (pintype "bidirectional"))
      (node (ref "R6") (pin "2") (pinfunction "2_2") (pintype "passive"))
    )
    (net (code "38") (name "Net-(MCU_SF-D-{slash}RF3)") (class "Default")
      (node (ref "MCU_SF") (pin "15") (pinfunction "D-/RF3_15") (pintype "bidirectional"))
      (node (ref "R7") (pin "2") (pinfunction "2_2") (pintype "passive"))
    )
    (net (code "39") (name "Net-(MCU_SF-OSC1{slash}CLKI{slash}RP10{slash}RA7)") (class "Default")
      (node (ref "C4") (pin "1") (pinfunction "1_1") (pintype "passive"))
      (node (ref "MCU_SF") (pin "39") (pinfunction "OSC1/CLKI/RP10/RA7_39") (pintype "bidirectional"))
      (node (ref "XTAL1") (pin "1") (pinfunction "1_1") (pintype "passive"))
    )
    (net (code "40") (name "Net-(MCU_SF-OSC2{slash}CLKO{slash}RP6{slash}RA6)") (class "Default")
      (node (ref "C5") (pin "1") (pinfunction "1_1") (pintype "passive"))
      (node (ref "MCU_SF") (pin "40") (pinfunction "OSC2/CLKO/RP6/RA6_40") (pintype "bidirectional"))
      (node (ref "XTAL1") (pin "2") (pinfunction "2_2") (pintype "passive"))
    )
    (net (code "41") (name "Net-(MCU_SF-VCAP)") (class "Default")
      (node (ref "C7") (pin "1") (pinfunction "1_1") (pintype "passive"))
      (node (ref "MCU_SF") (pin "10") (pinfunction "VCAP_10") (pintype "bidirectional"))
    )
    (net (code "42") (name "Net-(MOS1-D1)") (class "Default")
      (node (ref "MOS1") (pin "6") (pinfunction "D1_6") (pintype "input"))
      (node (ref "OCP1") (pin "7") (pinfunction "SENSE_7") (pintype "bidirectional"))
      (node (ref "R3") (pin "2") (pinfunction "2_2") (pintype "passive"))
    )
    (net (code "43") (name "Net-(MOS1-G1)") (class "Default")
      (node (ref "MOS1") (pin "2") (pinfunction "G1_2") (pintype "input"))
      (node (ref "OCP1") (pin "6") (pinfunction "GATE_6") (pintype "bidirectional"))
    )
    (net (code "44") (name "Net-(MOS2-D1)") (class "Default")
      (node (ref "MOS2") (pin "6") (pinfunction "D1_6") (pintype "input"))
      (node (ref "OCP2") (pin "7") (pinfunction "SENSE_7") (pintype "bidirectional"))
      (node (ref "R5") (pin "2") (pinfunction "2_2") (pintype "passive"))
    )
    (net (code "45") (name "Net-(MOS2-G1)") (class "Default")
      (node (ref "MOS2") (pin "2") (pinfunction "G1_2") (pintype "input"))
      (node (ref "OCP2") (pin "6") (pinfunction "GATE_6") (pintype "bidirectional"))
    )
    (net (code "46") (name "Net-(OCP1-ON)") (class "Default")
      (node (ref "OCP1") (pin "4") (pinfunction "ON_4") (pintype "bidirectional"))
      (node (ref "Q2") (pin "3") (pinfunction "C_3") (pintype "passive"))
      (node (ref "Q3") (pin "3") (pinfunction "C_3") (pintype "passive"))
      (node (ref "R2") (pin "1") (pinfunction "1_1") (pintype "passive"))
    )
    (net (code "47") (name "Net-(OCP2-ON)") (class "Default")
      (node (ref "OCP2") (pin "4") (pinfunction "ON_4") (pintype "bidirectional"))
      (node (ref "Q4") (pin "3") (pinfunction "C_3") (pintype "passive"))
      (node (ref "R4") (pin "1") (pinfunction "1_1") (pintype "passive"))
    )
    (net (code "48") (name "Net-(OPAMP1A-+IN)") (class "Default")
      (node (ref "C30") (pin "2") (pinfunction "2_2") (pintype "passive"))
      (node (ref "OPAMP1") (pin "3") (pinfunction "+IN_3") (pintype "input"))
      (node (ref "R31") (pin "2") (pinfunction "2_2") (pintype "passive"))
    )
    (net (code "49") (name "Net-(OPAMP1A--IN)") (class "Default")
      (node (ref "OPAMP1") (pin "2") (pinfunction "-IN_2") (pintype "input"))
      (node (ref "R37") (pin "1") (pinfunction "1_1") (pintype "passive"))
      (node (ref "R38") (pin "2") (pinfunction "2_2") (pintype "passive"))
    )
    (net (code "50") (name "Net-(OPAMP1B-+IN)") (class "Default")
      (node (ref "OPAMP1") (pin "5") (pinfunction "+IN_5") (pintype "input"))
      (node (ref "R28") (pin "1") (pinfunction "1_1") (pintype "passive"))
      (node (ref "R30") (pin "2") (pinfunction "2_2") (pintype "passive"))
    )
    (net (code "51") (name "Net-(Q1-C)") (class "Default")
      (node (ref "Q1") (pin "3") (pinfunction "C_3") (pintype "passive"))
      (node (ref "TRX2") (pin "5") (pinfunction "PTT_5") (pintype "input"))
    )
    (net (code "52") (name "Net-(R17-Pad1)") (class "Default")
      (node (ref "R17") (pin "1") (pinfunction "1_1") (pintype "passive"))
      (node (ref "SFD1") (pin "A") (pinfunction "A_A") (pintype "passive"))
    )
    (net (code "53") (name "Net-(R33-CW)") (class "Default")
      (node (ref "R33") (pin "3") (pinfunction "CW_3") (pintype "passive"))
      (node (ref "R34") (pin "1") (pinfunction "1_1") (pintype "passive"))
      (node (ref "R41") (pin "1") (pinfunction "1_1") (pintype "passive"))
    )
    (net (code "54") (name "Net-(R33-WIPER)") (class "Default")
      (node (ref "C32") (pin "1") (pinfunction "1_1") (pintype "passive"))
      (node (ref "R33") (pin "2") (pinfunction "WIPER_2") (pintype "passive"))
    )
    (net (code "55") (name "Net-(TRX1-ANT)") (class "Default")
      (node (ref "MCX1") (pin "1") (pinfunction "1_1") (pintype "bidirectional"))
      (node (ref "TRX1") (pin "P$2") (pinfunction "ANT_P$2") (pintype "bidirectional"))
    )
    (net (code "56") (name "Net-(TRX1-RSSI)") (class "Default")
      (node (ref "R27") (pin "2") (pinfunction "2_2") (pintype "passive"))
      (node (ref "TRX1") (pin "P$11") (pinfunction "RSSI_P$11") (pintype "bidirectional"))
    )
    (net (code "57") (name "Net-(TRX2-H{slash}L)") (class "Default")
      (node (ref "R1") (pin "2") (pinfunction "2_2") (pintype "passive"))
      (node (ref "TRX2") (pin "7") (pinfunction "H/L_7") (pintype "input"))
    )
    (net (code "58") (name "PA1") (class "Default")
      (node (ref "MCU_APRS") (pin "36") (pinfunction "PA1_36") (pintype "bidirectional"))
      (node (ref "R25") (pin "1") (pinfunction "1_1") (pintype "passive"))
      (node (ref "R26") (pin "2") (pinfunction "2_2") (pintype "passive"))
    )
    (net (code "59") (name "PD0_RXA") (class "Default")
      (node (ref "CN1") (pin "8") (pinfunction "8_8") (pintype "bidirectional"))
      (node (ref "JP1") (pin "P$7") (pinfunction "P$7_P$7") (pintype "bidirectional"))
      (node (ref "MCU_APRS") (pin "9") (pinfunction "PD0_9") (pintype "bidirectional"))
    )
    (net (code "60") (name "PD1_TXA") (class "Default")
      (node (ref "CN1") (pin "9") (pinfunction "9_9") (pintype "bidirectional"))
      (node (ref "JP1") (pin "P$5") (pinfunction "P$5_P$5") (pintype "bidirectional"))
      (node (ref "MCU_APRS") (pin "10") (pinfunction "PD1_10") (pintype "bidirectional"))
    )
    (net (code "61") (name "PGC") (class "Default")
      (node (ref "CN1") (pin "1") (pinfunction "1_1") (pintype "bidirectional"))
      (node (ref "JP1") (pin "P$17") (pinfunction "P$17_P$17") (pintype "bidirectional"))
      (node (ref "MCU_SF") (pin "42") (pinfunction "CTED5/PGC/RB6_42") (pintype "bidirectional"))
    )
    (net (code "62") (name "PGD") (class "Default")
      (node (ref "CN1") (pin "2") (pinfunction "2_2") (pintype "bidirectional"))
      (node (ref "JP1") (pin "P$15") (pinfunction "P$15_P$15") (pintype "bidirectional"))
      (node (ref "MCU_SF") (pin "37") (pinfunction "CTED6/PGD/RB7_37") (pintype "bidirectional"))
    )
    (net (code "63") (name "PTT") (class "Default")
      (node (ref "MCU_APRS") (pin "13") (pinfunction "PD4_13") (pintype "bidirectional"))
      (node (ref "Q1") (pin "2") (pinfunction "B_2") (pintype "passive"))
      (node (ref "R44") (pin "2") (pinfunction "2_2") (pintype "passive"))
    )
    (net (code "64") (name "RFOUT") (class "Default")
      (node (ref "R42") (pin "2") (pinfunction "2_2") (pintype "passive"))
      (node (ref "TRX1") (pin "P$13") (pinfunction "AF_P$13") (pintype "bidirectional"))
    )
    (net (code "65") (name "RF_TRX") (class "Default")
      (node (ref "C14") (pin "1") (pinfunction "1_1") (pintype "passive"))
      (node (ref "L3") (pin "2") (pinfunction "2_2") (pintype "passive"))
      (node (ref "TRX2") (pin "12") (pinfunction "ANT_12") (pintype "passive"))
    )
    (net (code "66") (name "RSSI") (class "Default")
      (node (ref "R27") (pin "1") (pinfunction "1_1") (pintype "passive"))
    )
    (net (code "67") (name "RXD") (class "Default")
      (node (ref "R43") (pin "2") (pinfunction "2_2") (pintype "passive"))
      (node (ref "TRX1") (pin "P$12") (pinfunction "RXD_P$12") (pintype "bidirectional"))
    )
    (net (code "68") (name "SFWARD_3V3_2") (class "Default")
      (node (ref "C1") (pin "1") (pinfunction "1_1") (pintype "passive"))
      (node (ref "C10") (pin "1") (pinfunction "1_1") (pintype "passive"))
      (node (ref "C11") (pin "1") (pinfunction "1_1") (pintype "passive"))
      (node (ref "C12") (pin "1") (pinfunction "1_1") (pintype "passive"))
      (node (ref "C3") (pin "1") (pinfunction "1_1") (pintype "passive"))
      (node (ref "C35") (pin "1") (pinfunction "1_1") (pintype "passive"))
      (node (ref "C6") (pin "1") (pinfunction "1_1") (pintype "passive"))
      (node (ref "C8") (pin "1") (pinfunction "1_1") (pintype "passive"))
      (node (ref "C9") (pin "1") (pinfunction "1_1") (pintype "passive"))
      (node (ref "FM_SF") (pin "2") (pinfunction "VCC_2") (pintype "input"))
      (node (ref "JP1") (pin "P$9") (pinfunction "P$9_P$9") (pintype "bidirectional"))
      (node (ref "MCU_SF") (pin "17") (pinfunction "VUSB3V3_17") (pintype "bidirectional"))
      (node (ref "MCU_SF") (pin "19") (pinfunction "AVDD_19") (pintype "bidirectional"))
      (node (ref "MCU_SF") (pin "26") (pinfunction "VDD_1_26") (pintype "bidirectional"))
      (node (ref "MCU_SF") (pin "38") (pinfunction "VDD_2_38") (pintype "bidirectional"))
      (node (ref "MCU_SF") (pin "57") (pinfunction "VDD_3_57") (pintype "bidirectional"))
      (node (ref "MOS2") (pin "1") (pinfunction "S1_1") (pintype "input"))
      (node (ref "OCP2") (pin "3") (pinfunction "OUT_3") (pintype "bidirectional"))
      (node (ref "R10") (pin "1") (pinfunction "1_1") (pintype "passive"))
      (node (ref "R11") (pin "1") (pinfunction "1_1") (pintype "passive"))
      (node (ref "R12") (pin "1") (pinfunction "1_1") (pintype "passive"))
      (node (ref "R13") (pin "1") (pinfunction "1_1") (pintype "passive"))
      (node (ref "R14") (pin "1") (pinfunction "1_1") (pintype "passive"))
      (node (ref "R15") (pin "1") (pinfunction "1_1") (pintype "passive"))
      (node (ref "R16") (pin "1") (pinfunction "1_1") (pintype "passive"))
      (node (ref "R9") (pin "1") (pinfunction "1_1") (pintype "passive"))
      (node (ref "U2") (pin "5") (pinfunction "VCC_5") (pintype "power_in"))
    )
    (net (code "69") (name "SPI_FM_CS") (class "Default")
      (node (ref "FM_SF") (pin "7") (pinfunction "S#_7") (pintype "input"))
      (node (ref "MCU_SF") (pin "22") (pinfunction "SEG21/VREF-/AN2/RP2/RA2_22") (pintype "bidirectional"))
      (node (ref "R13") (pin "2") (pinfunction "2_2") (pintype "passive"))
    )
    (net (code "70") (name "SPI_MISO") (class "Default")
      (node (ref "FM_SF") (pin "8") (pinfunction "DQ1_8") (pintype "input"))
      (node (ref "MCU_SF") (pin "23") (pinfunction "SEG18/AN1/RP1/RA1_23") (pintype "bidirectional"))
      (node (ref "R11") (pin "2") (pinfunction "2_2") (pintype "passive"))
    )
    (net (code "71") (name "SPI_MOSI") (class "Default")
      (node (ref "FM_SF") (pin "15") (pinfunction "DQ0_15") (pintype "input"))
      (node (ref "MCU_SF") (pin "24") (pinfunction "SEG19/AN0/AN1-/RP0/RA0_24") (pintype "bidirectional"))
      (node (ref "R12") (pin "2") (pinfunction "2_2") (pintype "passive"))
    )
    (net (code "72") (name "SPI_SCK") (class "Default")
      (node (ref "FM_SF") (pin "16") (pinfunction "C_16") (pintype "input"))
      (node (ref "MCU_SF") (pin "21") (pinfunction "VREF+/AN3/RP3/RA3_21") (pintype "bidirectional"))
      (node (ref "R14") (pin "2") (pinfunction "2_2") (pintype "passive"))
    )
    (net (code "73") (name "SUP_3V3_2") (class "Default")
      (node (ref "CN1") (pin "25") (pinfunction "25_25") (pintype "bidirectional"))
      (node (ref "CN1") (pin "26") (pinfunction "26_26") (pintype "bidirectional"))
      (node (ref "OCP2") (pin "8") (pinfunction "IN_8") (pintype "bidirectional"))
      (node (ref "R4") (pin "2") (pinfunction "2_2") (pintype "passive"))
      (node (ref "R5") (pin "1") (pinfunction "1_1") (pintype "passive"))
    )
    (net (code "74") (name "SUP_5V0") (class "Default")
      (node (ref "CN1") (pin "15") (pinfunction "15_15") (pintype "bidirectional"))
      (node (ref "CN1") (pin "16") (pinfunction "16_16") (pintype "bidirectional"))
      (node (ref "OCP1") (pin "8") (pinfunction "IN_8") (pintype "bidirectional"))
      (node (ref "R2") (pin "2") (pinfunction "2_2") (pintype "passive"))
      (node (ref "R3") (pin "1") (pinfunction "1_1") (pintype "passive"))
    )
    (net (code "75") (name "TNC_RX") (class "Default")
      (node (ref "JP1") (pin "P$3") (pinfunction "P$3_P$3") (pintype "bidirectional"))
      (node (ref "MCU_APRS") (pin "11") (pinfunction "PD2_11") (pintype "bidirectional"))
      (node (ref "U1") (pin "4") (pinfunction "Y_4") (pintype "output"))
    )
    (net (code "76") (name "TNC_TX") (class "Default")
      (node (ref "JP1") (pin "P$1") (pinfunction "P$1_P$1") (pintype "bidirectional"))
      (node (ref "MCU_APRS") (pin "12") (pinfunction "PD3_12") (pintype "bidirectional"))
      (node (ref "U2") (pin "2") (pinfunction "A_2") (pintype "input"))
    )
    (net (code "77") (name "TRX1_AFOUT") (class "Default")
      (node (ref "C26") (pin "2") (pinfunction "2_2") (pintype "passive"))
      (node (ref "JP1") (pin "P$10") (pinfunction "P$10_P$10") (pintype "bidirectional"))
      (node (ref "R42") (pin "1") (pinfunction "1_1") (pintype "passive"))
      (node (ref "R43") (pin "1") (pinfunction "1_1") (pintype "passive"))
      (node (ref "TRX2") (pin "3") (pinfunction "AF_OUT_3") (pintype "output"))
    )
    (net (code "78") (name "TRX1_RXSELECT") (class "Default")
      (node (ref "MCU_APRS") (pin "40") (pinfunction "PB0_40") (pintype "bidirectional"))
      (node (ref "OPAMP1") (pin "6") (pinfunction "-IN_6") (pintype "input"))
      (node (ref "R21") (pin "1") (pinfunction "1_1") (pintype "passive"))
      (node (ref "R29") (pin "2") (pinfunction "2_2") (pintype "passive"))
      (node (ref "R44") (pin "1") (pinfunction "1_1") (pintype "passive"))
      (node (ref "R45") (pin "1") (pinfunction "1_1") (pintype "passive"))
      (node (ref "R45") (pin "2") (pinfunction "2_2") (pintype "passive"))
      (node (ref "TRX1") (pin "P$16") (pinfunction "RXSELECT_P$16") (pintype "bidirectional"))
    )
    (net (code "79") (name "TRX1_TXD") (class "Default")
      (node (ref "OPAMP1") (pin "1") (pinfunction "OUT_1") (pintype "output"))
      (node (ref "R37") (pin "2") (pinfunction "2_2") (pintype "passive"))
      (node (ref "R39") (pin "2") (pinfunction "2_2") (pintype "passive"))
      (node (ref "TRX1") (pin "P$14") (pinfunction "TXD_P$14") (pintype "bidirectional"))
    )
    (net (code "80") (name "TRX1_TXSELECT") (class "Default")
      (node (ref "OPAMP1") (pin "7") (pinfunction "OUT_7") (pintype "output"))
      (node (ref "TRX1") (pin "P$15") (pinfunction "TXSELECT_P$15") (pintype "bidirectional"))
    )
    (net (code "81") (name "TRX_IN") (class "Default")
      (node (ref "JP1") (pin "P$8") (pinfunction "P$8_P$8") (pintype "bidirectional"))
      (node (ref "R39") (pin "1") (pinfunction "1_1") (pintype "passive"))
      (node (ref "R40") (pin "1") (pinfunction "1_1") (pintype "passive"))
      (node (ref "TRX2") (pin "18") (pinfunction "MIC_IN_18") (pintype "input"))
    )
    (net (code "82") (name "TRX_UART_RXD") (class "Default")
      (node (ref "JP1") (pin "P$22") (pinfunction "P$22_P$22") (pintype "bidirectional"))
      (node (ref "TRX2") (pin "16") (pinfunction "RXD_16") (pintype "input"))
    )
    (net (code "83") (name "TRX_UART_TXD") (class "Default")
      (node (ref "JP1") (pin "P$24") (pinfunction "P$24_P$24") (pintype "bidirectional"))
      (node (ref "TRX2") (pin "17") (pinfunction "TXD_17") (pintype "output"))
    )
    (net (code "84") (name "unconnected-(CN1-Pad4)") (class "Default")
      (node (ref "CN1") (pin "4") (pinfunction "4_4") (pintype "bidirectional"))
    )
    (net (code "85") (name "unconnected-(CN1-Pad5)") (class "Default")
      (node (ref "CN1") (pin "5") (pinfunction "5_5") (pintype "bidirectional"))
    )
    (net (code "86") (name "unconnected-(CN1-Pad6)") (class "Default")
      (node (ref "CN1") (pin "6") (pinfunction "6_6") (pintype "bidirectional"))
    )
    (net (code "87") (name "unconnected-(CN1-Pad7)") (class "Default")
      (node (ref "CN1") (pin "7") (pinfunction "7_7") (pintype "bidirectional"))
    )
    (net (code "88") (name "unconnected-(CN1-Pad10)") (class "Default")
      (node (ref "CN1") (pin "10") (pinfunction "10_10") (pintype "bidirectional"))
    )
    (net (code "89") (name "unconnected-(CN1-Pad11)") (class "Default")
      (node (ref "CN1") (pin "11") (pinfunction "11_11") (pintype "bidirectional"))
    )
    (net (code "90") (name "unconnected-(CN1-Pad12)") (class "Default")
      (node (ref "CN1") (pin "12") (pinfunction "12_12") (pintype "bidirectional"))
    )
    (net (code "91") (name "unconnected-(CN1-Pad21)") (class "Default")
      (node (ref "CN1") (pin "21") (pinfunction "21_21") (pintype "bidirectional"))
    )
    (net (code "92") (name "unconnected-(CN1-Pad22)") (class "Default")
      (node (ref "CN1") (pin "22") (pinfunction "22_22") (pintype "bidirectional"))
    )
    (net (code "93") (name "unconnected-(CN1-Pad23)") (class "Default")
      (node (ref "CN1") (pin "23") (pinfunction "23_23") (pintype "bidirectional"))
    )
    (net (code "94") (name "unconnected-(CN1-Pad24)") (class "Default")
      (node (ref "CN1") (pin "24") (pinfunction "24_24") (pintype "bidirectional"))
    )
    (net (code "95") (name "unconnected-(CN1-Pad27)") (class "Default")
      (node (ref "CN1") (pin "27") (pinfunction "27_27") (pintype "bidirectional"))
    )
    (net (code "96") (name "unconnected-(CN1-Pad28)") (class "Default")
      (node (ref "CN1") (pin "28") (pinfunction "28_28") (pintype "bidirectional"))
    )
    (net (code "97") (name "unconnected-(CN1-Pad29)") (class "Default")
      (node (ref "CN1") (pin "29") (pinfunction "29_29") (pintype "bidirectional"))
    )
    (net (code "98") (name "unconnected-(CN1-Pad30)") (class "Default")
      (node (ref "CN1") (pin "30") (pinfunction "30_30") (pintype "bidirectional"))
    )
    (net (code "99") (name "unconnected-(CN1-Pad31)") (class "Default")
      (node (ref "CN1") (pin "31") (pinfunction "31_31") (pintype "bidirectional"))
    )
    (net (code "100") (name "unconnected-(CN1-Pad32)") (class "Default")
      (node (ref "CN1") (pin "32") (pinfunction "32_32") (pintype "bidirectional"))
    )
    (net (code "101") (name "unconnected-(CN1-Pad33)") (class "Default")
      (node (ref "CN1") (pin "33") (pinfunction "33_33") (pintype "bidirectional"))
    )
    (net (code "102") (name "unconnected-(CN1-Pad34)") (class "Default")
      (node (ref "CN1") (pin "34") (pinfunction "34_34") (pintype "bidirectional"))
    )
    (net (code "103") (name "unconnected-(CN1-Pad35)") (class "Default")
      (node (ref "CN1") (pin "35") (pinfunction "35_35") (pintype "bidirectional"))
    )
    (net (code "104") (name "unconnected-(CN1-Pad36)") (class "Default")
      (node (ref "CN1") (pin "36") (pinfunction "36_36") (pintype "bidirectional"))
    )
    (net (code "105") (name "unconnected-(CN1-Pad37)") (class "Default")
      (node (ref "CN1") (pin "37") (pinfunction "37_37") (pintype "bidirectional"))
    )
    (net (code "106") (name "unconnected-(CN1-Pad38)") (class "Default")
      (node (ref "CN1") (pin "38") (pinfunction "38_38") (pintype "bidirectional"))
    )
    (net (code "107") (name "unconnected-(CN1-Pad39)") (class "Default")
      (node (ref "CN1") (pin "39") (pinfunction "39_39") (pintype "bidirectional"))
    )
    (net (code "108") (name "unconnected-(CN1-Pad40)") (class "Default")
      (node (ref "CN1") (pin "40") (pinfunction "40_40") (pintype "bidirectional"))
    )
    (net (code "109") (name "unconnected-(CN1-Pad41)") (class "Default")
      (node (ref "CN1") (pin "41") (pinfunction "41_41") (pintype "bidirectional"))
    )
    (net (code "110") (name "unconnected-(CN1-Pad42)") (class "Default")
      (node (ref "CN1") (pin "42") (pinfunction "42_42") (pintype "bidirectional"))
    )
    (net (code "111") (name "unconnected-(CN1-Pad43)") (class "Default")
      (node (ref "CN1") (pin "43") (pinfunction "43_43") (pintype "bidirectional"))
    )
    (net (code "112") (name "unconnected-(CN1-Pad44)") (class "Default")
      (node (ref "CN1") (pin "44") (pinfunction "44_44") (pintype "bidirectional"))
    )
    (net (code "113") (name "unconnected-(CN1-Pad45)") (class "Default")
      (node (ref "CN1") (pin "45") (pinfunction "45_45") (pintype "bidirectional"))
    )
    (net (code "114") (name "unconnected-(CN1-Pad46)") (class "Default")
      (node (ref "CN1") (pin "46") (pinfunction "46_46") (pintype "bidirectional"))
    )
    (net (code "115") (name "unconnected-(CN1-Pad47)") (class "Default")
      (node (ref "CN1") (pin "47") (pinfunction "47_47") (pintype "bidirectional"))
    )
    (net (code "116") (name "unconnected-(CN1-Pad48)") (class "Default")
      (node (ref "CN1") (pin "48") (pinfunction "48_48") (pintype "bidirectional"))
    )
    (net (code "117") (name "unconnected-(CN1-Pad49)") (class "Default")
      (node (ref "CN1") (pin "49") (pinfunction "49_49") (pintype "bidirectional"))
    )
    (net (code "118") (name "unconnected-(CN1-Pad50)") (class "Default")
      (node (ref "CN1") (pin "50") (pinfunction "50_50") (pintype "bidirectional"))
    )
    (net (code "119") (name "unconnected-(FM_SF-DNU(1)-Pad4)") (class "Default")
      (node (ref "FM_SF") (pin "4") (pinfunction "DNU(1)_4") (pintype "input"))
    )
    (net (code "120") (name "unconnected-(FM_SF-DNU(2)-Pad5)") (class "Default")
      (node (ref "FM_SF") (pin "5") (pinfunction "DNU(2)_5") (pintype "input"))
    )
    (net (code "121") (name "unconnected-(FM_SF-DNU(3)-Pad6)") (class "Default")
      (node (ref "FM_SF") (pin "6") (pinfunction "DNU(3)_6") (pintype "input"))
    )
    (net (code "122") (name "unconnected-(FM_SF-DNU(4)-Pad11)") (class "Default")
      (node (ref "FM_SF") (pin "11") (pinfunction "DNU(4)_11") (pintype "input"))
    )
    (net (code "123") (name "unconnected-(FM_SF-DNU(5)-Pad12)") (class "Default")
      (node (ref "FM_SF") (pin "12") (pinfunction "DNU(5)_12") (pintype "input"))
    )
    (net (code "124") (name "unconnected-(FM_SF-DNU(6)-Pad13)") (class "Default")
      (node (ref "FM_SF") (pin "13") (pinfunction "DNU(6)_13") (pintype "input"))
    )
    (net (code "125") (name "unconnected-(FM_SF-DNU(7)-Pad14)") (class "Default")
      (node (ref "FM_SF") (pin "14") (pinfunction "DNU(7)_14") (pintype "input"))
    )
    (net (code "126") (name "unconnected-(JP1-PadP$4)") (class "Default")
      (node (ref "JP1") (pin "P$4") (pinfunction "P$4_P$4") (pintype "bidirectional"))
    )
    (net (code "127") (name "unconnected-(JP1-PadP$6)") (class "Default")
      (node (ref "JP1") (pin "P$6") (pinfunction "P$6_P$6") (pintype "bidirectional"))
    )
    (net (code "128") (name "unconnected-(JP1-PadP$18)") (class "Default")
      (node (ref "JP1") (pin "P$18") (pinfunction "P$18_P$18") (pintype "bidirectional"))
    )
    (net (code "129") (name "unconnected-(JP1-PadP$20)") (class "Default")
      (node (ref "JP1") (pin "P$20") (pinfunction "P$20_P$20") (pintype "bidirectional"))
    )
    (net (code "130") (name "unconnected-(JP1-PadP$21)") (class "Default")
      (node (ref "JP1") (pin "P$21") (pinfunction "P$21_P$21") (pintype "bidirectional"))
    )
    (net (code "131") (name "unconnected-(JP1-PadP$23)") (class "Default")
      (node (ref "JP1") (pin "P$23") (pinfunction "P$23_P$23") (pintype "bidirectional"))
    )
    (net (code "132") (name "unconnected-(MCU_APRS-PA3-Pad34)") (class "Default")
      (node (ref "MCU_APRS") (pin "34") (pinfunction "PA3_34") (pintype "bidirectional"))
    )
    (net (code "133") (name "unconnected-(MCU_APRS-PA4-Pad33)") (class "Default")
      (node (ref "MCU_APRS") (pin "33") (pinfunction "PA4_33") (pintype "bidirectional"))
    )
    (net (code "134") (name "unconnected-(MCU_APRS-PA5-Pad32)") (class "Default")
      (node (ref "MCU_APRS") (pin "32") (pinfunction "PA5_32") (pintype "bidirectional"))
    )
    (net (code "135") (name "unconnected-(MCU_APRS-PA6-Pad31)") (class "Default")
      (node (ref "MCU_APRS") (pin "31") (pinfunction "PA6_31") (pintype "bidirectional"))
    )
    (net (code "136") (name "unconnected-(MCU_APRS-PB4-Pad44)") (class "Default")
      (node (ref "MCU_APRS") (pin "44") (pinfunction "PB4_44") (pintype "bidirectional"))
    )
    (net (code "137") (name "unconnected-(MCU_APRS-PB5-Pad1)") (class "Default")
      (node (ref "MCU_APRS") (pin "1") (pinfunction "PB5_1") (pintype "bidirectional"))
    )
    (net (code "138") (name "unconnected-(MCU_APRS-PB6-Pad2)") (class "Default")
      (node (ref "MCU_APRS") (pin "2") (pinfunction "PB6_2") (pintype "bidirectional"))
    )
    (net (code "139") (name "unconnected-(MCU_APRS-PB7-Pad3)") (class "Default")
      (node (ref "MCU_APRS") (pin "3") (pinfunction "PB7_3") (pintype "bidirectional"))
    )
    (net (code "140") (name "unconnected-(MCU_APRS-PC0-Pad19)") (class "Default")
      (node (ref "MCU_APRS") (pin "19") (pinfunction "PC0_19") (pintype "bidirectional"))
    )
    (net (code "141") (name "unconnected-(MCU_APRS-PC1-Pad20)") (class "Default")
      (node (ref "MCU_APRS") (pin "20") (pinfunction "PC1_20") (pintype "bidirectional"))
    )
    (net (code "142") (name "unconnected-(MCU_APRS-PC2-Pad21)") (class "Default")
      (node (ref "MCU_APRS") (pin "21") (pinfunction "PC2_21") (pintype "bidirectional"))
    )
    (net (code "143") (name "unconnected-(MCU_APRS-PC3-Pad22)") (class "Default")
      (node (ref "MCU_APRS") (pin "22") (pinfunction "PC3_22") (pintype "bidirectional"))
    )
    (net (code "144") (name "unconnected-(MCU_APRS-PC4-Pad23)") (class "Default")
      (node (ref "MCU_APRS") (pin "23") (pinfunction "PC4_23") (pintype "bidirectional"))
    )
    (net (code "145") (name "unconnected-(MCU_APRS-PC5-Pad24)") (class "Default")
      (node (ref "MCU_APRS") (pin "24") (pinfunction "PC5_24") (pintype "bidirectional"))
    )
    (net (code "146") (name "unconnected-(MCU_APRS-PC6-Pad25)") (class "Default")
      (node (ref "MCU_APRS") (pin "25") (pinfunction "PC6_25") (pintype "bidirectional"))
    )
    (net (code "147") (name "unconnected-(MCU_APRS-PC7-Pad26)") (class "Default")
      (node (ref "MCU_APRS") (pin "26") (pinfunction "PC7_26") (pintype "bidirectional"))
    )
    (net (code "148") (name "unconnected-(MCU_APRS-PD6-Pad15)") (class "Default")
      (node (ref "MCU_APRS") (pin "15") (pinfunction "PD6_15") (pintype "bidirectional"))
    )
    (net (code "149") (name "unconnected-(MCU_APRS-PD7-Pad16)") (class "Default")
      (node (ref "MCU_APRS") (pin "16") (pinfunction "PD7_16") (pintype "bidirectional"))
    )
    (net (code "150") (name "unconnected-(MCU_APRS-~{RESET}-Pad4)") (class "Default")
      (node (ref "MCU_APRS") (pin "4") (pinfunction "~{RESET}_4") (pintype "input"))
    )
    (net (code "151") (name "unconnected-(MCU_SF-COM0{slash}RP33{slash}REFO1{slash}RE3-Pad63)") (class "Default")
      (node (ref "MCU_SF") (pin "63") (pinfunction "COM0/RP33/REFO1/RE3_63") (pintype "bidirectional"))
    )
    (net (code "152") (name "unconnected-(MCU_SF-COM1{slash}RP32{slash}RE4-Pad62)") (class "Default")
      (node (ref "MCU_SF") (pin "62") (pinfunction "COM1/RP32/RE4_62") (pintype "bidirectional"))
    )
    (net (code "153") (name "unconnected-(MCU_SF-COM2{slash}RP37{slash}RE5-Pad61)") (class "Default")
      (node (ref "MCU_SF") (pin "61") (pinfunction "COM2/RP37/RE5_61") (pintype "bidirectional"))
    )
    (net (code "154") (name "unconnected-(MCU_SF-COM5{slash}SEG29{slash}AN19{slash}RP39{slash}RG1-Pad4)") (class "Default")
      (node (ref "MCU_SF") (pin "4") (pinfunction "COM5/SEG29/AN19/RP39/RG1_4") (pintype "bidirectional"))
    )
    (net (code "155") (name "unconnected-(MCU_SF-COM6{slash}SEG30{slash}AN18{slash}C3INA{slash}RP42{slash}RG2-Pad5)") (class "Default")
      (node (ref "MCU_SF") (pin "5") (pinfunction "COM6/SEG30/AN18/C3INA/RP42/RG2_5") (pintype "bidirectional"))
    )
    (net (code "156") (name "unconnected-(MCU_SF-COM7{slash}SEG31{slash}AN17{slash}C3INB{slash}RP43{slash}RG3-Pad6)") (class "Default")
      (node (ref "MCU_SF") (pin "6") (pinfunction "COM7/SEG31/AN17/C3INB/RP43/RG3_6") (pintype "bidirectional"))
    )
    (net (code "157") (name "unconnected-(MCU_SF-LCDBIAS0{slash}RP31{slash}RE7-Pad59)") (class "Default")
      (node (ref "MCU_SF") (pin "59") (pinfunction "LCDBIAS0/RP31/RE7_59") (pintype "bidirectional"))
    )
    (net (code "158") (name "unconnected-(MCU_SF-LCDBIAS3{slash}RP30{slash}C-Pad64)") (class "Default")
      (node (ref "MCU_SF") (pin "64") (pinfunction "LCDBIAS3/RP30/C_64") (pintype "bidirectional"))
    )
    (net (code "159") (name "unconnected-(MCU_SF-SEG0{slash}RP20{slash}PSP0{slash}RD0-Pad58)") (class "Default")
      (node (ref "MCU_SF") (pin "58") (pinfunction "SEG0/RP20/PSP0/RD0_58") (pintype "bidirectional"))
    )
    (net (code "160") (name "unconnected-(MCU_SF-SEG1{slash}RP21{slash}PSP1{slash}RD1-Pad55)") (class "Default")
      (node (ref "MCU_SF") (pin "55") (pinfunction "SEG1/RP21/PSP1/RD1_55") (pintype "bidirectional"))
    )
    (net (code "161") (name "unconnected-(MCU_SF-SEG2{slash}RP22{slash}PSP2{slash}RD2-Pad54)") (class "Default")
      (node (ref "MCU_SF") (pin "54") (pinfunction "SEG2/RP22/PSP2/RD2_54") (pintype "bidirectional"))
    )
    (net (code "162") (name "unconnected-(MCU_SF-SEG3{slash}RP23{slash}PSP3{slash}RD3-Pad53)") (class "Default")
      (node (ref "MCU_SF") (pin "53") (pinfunction "SEG3/RP23/PSP3/RD3_53") (pintype "bidirectional"))
    )
    (net (code "163") (name "unconnected-(MCU_SF-SEG4{slash}RP24{slash}PSP4{slash}RD4-Pad52)") (class "Default")
      (node (ref "MCU_SF") (pin "52") (pinfunction "SEG4/RP24/PSP4/RD4_52") (pintype "bidirectional"))
    )
    (net (code "164") (name "unconnected-(MCU_SF-SEG5{slash}SDA2{slash}RP25{slash}PSP5{slash}RD5-Pad51)") (class "Default")
      (node (ref "MCU_SF") (pin "51") (pinfunction "SEG5/SDA2/RP25/PSP5/RD5_51") (pintype "bidirectional"))
    )
    (net (code "165") (name "unconnected-(MCU_SF-SEG6{slash}SCL2{slash}RP26{slash}PSP6{slash}RD6-Pad50)") (class "Default")
      (node (ref "MCU_SF") (pin "50") (pinfunction "SEG6/SCL2/RP26/PSP6/RD6_50") (pintype "bidirectional"))
    )
    (net (code "166") (name "unconnected-(MCU_SF-SEG7{slash}RP27{slash}REFO2{slash}PSP7{slash}RD7-Pad49)") (class "Default")
      (node (ref "MCU_SF") (pin "49") (pinfunction "SEG7/RP27/REFO2/PSP7/RD7_49") (pintype "bidirectional"))
    )
    (net (code "167") (name "unconnected-(MCU_SF-SEG8{slash}RP13{slash}CTED4{slash}RB5-Pad43)") (class "Default")
      (node (ref "MCU_SF") (pin "43") (pinfunction "SEG8/RP13/CTED4/RB5_43") (pintype "bidirectional"))
    )
    (net (code "168") (name "unconnected-(MCU_SF-SEG9{slash}RP14{slash}CTED1{slash}RB2-Pad46)") (class "Default")
      (node (ref "MCU_SF") (pin "46") (pinfunction "SEG9/RP14/CTED1/RB2_46") (pintype "bidirectional"))
    )
    (net (code "169") (name "unconnected-(MCU_SF-SEG10{slash}RP7{slash}CTED2{slash}RB3-Pad45)") (class "Default")
      (node (ref "MCU_SF") (pin "45") (pinfunction "SEG10/RP7/CTED2/RB3_45") (pintype "bidirectional"))
    )
    (net (code "170") (name "unconnected-(MCU_SF-SEG11{slash}RP12{slash}CTED3{slash}RB4-Pad44)") (class "Default")
      (node (ref "MCU_SF") (pin "44") (pinfunction "SEG11/RP12/CTED3/RB4_44") (pintype "bidirectional"))
    )
    (net (code "171") (name "unconnected-(MCU_SF-SEG12{slash}RP16{slash}CTED10{slash}RC5-Pad36)") (class "Default")
      (node (ref "MCU_SF") (pin "36") (pinfunction "SEG12/RP16/CTED10/RC5_36") (pintype "bidirectional"))
    )
    (net (code "172") (name "unconnected-(MCU_SF-SEG13{slash}AN9{slash}RP11{slash}CTED7{slash}RC2-Pad33)") (class "Default")
      (node (ref "MCU_SF") (pin "33") (pinfunction "SEG13/AN9/RP11/CTED7/RC2_33") (pintype "bidirectional"))
    )
    (net (code "173") (name "unconnected-(MCU_SF-SEG14{slash}AN6{slash}RP4{slash}RA4-Pad28)") (class "Default")
      (node (ref "MCU_SF") (pin "28") (pinfunction "SEG14/AN6/RP4/RA4_28") (pintype "bidirectional"))
    )
    (net (code "174") (name "unconnected-(MCU_SF-SEG15{slash}AN4{slash}LVDIN{slash}C1INA{slash}C2INA{slash}C3INA{slash}RP5{slash}RA5-Pad27)") (class "Default")
      (node (ref "MCU_SF") (pin "27") (pinfunction "SEG15/AN4/LVDIN/C1INA/C2INA/C3INA/RP5/RA5_27") (pintype "bidirectional"))
    )
    (net (code "175") (name "unconnected-(MCU_SF-SEG16{slash}SDA1{slash}RP17{slash}CTED9{slash}RC4-Pad35)") (class "Default")
      (node (ref "MCU_SF") (pin "35") (pinfunction "SEG16/SDA1/RP17/CTED9/RC4_35") (pintype "bidirectional"))
    )
    (net (code "176") (name "unconnected-(MCU_SF-SEG17{slash}SCL1{slash}RP15{slash}CTED8{slash}RC3-Pad34)") (class "Default")
      (node (ref "MCU_SF") (pin "34") (pinfunction "SEG17/SCL1/RP15/CTED8/RC3_34") (pintype "bidirectional"))
    )
    (net (code "177") (name "unconnected-(MCU_SF-SEG20{slash}AN7{slash}CTMUI{slash}C2INB{slash}RP36{slash}RF2-Pad16)") (class "Default")
      (node (ref "MCU_SF") (pin "16") (pinfunction "SEG20/AN7/CTMUI/C2INB/RP36/RF2_16") (pintype "bidirectional"))
    )
    (net (code "178") (name "unconnected-(MCU_SF-SEG23{slash}CVREF{slash}AN10{slash}C1INB{slash}RP35{slash}RF5-Pad13)") (class "Default")
      (node (ref "MCU_SF") (pin "13") (pinfunction "SEG23/CVREF/AN10/C1INB/RP35/RF5_13") (pintype "bidirectional"))
    )
    (net (code "179") (name "unconnected-(MCU_SF-SEG24{slash}AN11{slash}C1INA{slash}RP40{slash}RF6-Pad12)") (class "Default")
      (node (ref "MCU_SF") (pin "12") (pinfunction "SEG24/AN11/C1INA/RP40/RF6_12") (pintype "bidirectional"))
    )
    (net (code "180") (name "unconnected-(MCU_SF-SEG25{slash}AN5{slash}RP38{slash}RF7-Pad11)") (class "Default")
      (node (ref "MCU_SF") (pin "11") (pinfunction "SEG25/AN5/RP38/RF7_11") (pintype "bidirectional"))
    )
    (net (code "181") (name "unconnected-(MCU_SF-SEG26{slash}AN16{slash}C3INC{slash}RP44{slash}RTCC{slash}RG4-Pad8)") (class "Default")
      (node (ref "MCU_SF") (pin "8") (pinfunction "SEG26/AN16/C3INC/RP44/RTCC/RG4_8") (pintype "bidirectional"))
    )
    (net (code "182") (name "unconnected-(MCU_SF-SOSCI{slash}RC1-Pad29)") (class "Default")
      (node (ref "MCU_SF") (pin "29") (pinfunction "SOSCI/RC1_29") (pintype "bidirectional"))
    )
    (net (code "183") (name "unconnected-(MCU_SF-SOSCO{slash}SCLKI{slash}PWRLCLK{slash}RC0-Pad30)") (class "Default")
      (node (ref "MCU_SF") (pin "30") (pinfunction "SOSCO/SCLKI/PWRLCLK/RC0_30") (pintype "bidirectional"))
    )
    (net (code "184") (name "unconnected-(MCU_SF-VBAT-Pad18)") (class "Default")
      (node (ref "MCU_SF") (pin "18") (pinfunction "VBAT_18") (pintype "bidirectional"))
    )
    (net (code "185") (name "unconnected-(MCU_SF-VLCAP1{slash}RP8{slash}CTED13{slash}INT0{slash}RB0-Pad48)") (class "Default")
      (node (ref "MCU_SF") (pin "48") (pinfunction "VLCAP1/RP8/CTED13/INT0/RB0_48") (pintype "bidirectional"))
    )
    (net (code "186") (name "unconnected-(MCU_SF-VLCAP2{slash}RP9{slash}RB1-Pad47)") (class "Default")
      (node (ref "MCU_SF") (pin "47") (pinfunction "VLCAP2/RP9/RB1_47") (pintype "bidirectional"))
    )
    (net (code "187") (name "unconnected-(MOS1-D2-Pad3)") (class "Default")
      (node (ref "MOS1") (pin "3") (pinfunction "D2_3") (pintype "input"))
    )
    (net (code "188") (name "unconnected-(MOS1-G2-Pad5)") (class "Default")
      (node (ref "MOS1") (pin "5") (pinfunction "G2_5") (pintype "input"))
    )
    (net (code "189") (name "unconnected-(MOS1-S2-Pad4)") (class "Default")
      (node (ref "MOS1") (pin "4") (pinfunction "S2_4") (pintype "input"))
    )
    (net (code "190") (name "unconnected-(MOS2-D2-Pad3)") (class "Default")
      (node (ref "MOS2") (pin "3") (pinfunction "D2_3") (pintype "input"))
    )
    (net (code "191") (name "unconnected-(MOS2-G2-Pad5)") (class "Default")
      (node (ref "MOS2") (pin "5") (pinfunction "G2_5") (pintype "input"))
    )
    (net (code "192") (name "unconnected-(MOS2-S2-Pad4)") (class "Default")
      (node (ref "MOS2") (pin "4") (pinfunction "S2_4") (pintype "input"))
    )
    (net (code "193") (name "unconnected-(OCP1-GATEP-Pad2)") (class "Default")
      (node (ref "OCP1") (pin "2") (pinfunction "GATEP_2") (pintype "bidirectional"))
    )
    (net (code "194") (name "unconnected-(OCP1-PWRGD-Pad5)") (class "Default")
      (node (ref "OCP1") (pin "5") (pinfunction "PWRGD_5") (pintype "bidirectional"))
    )
    (net (code "195") (name "unconnected-(OCP2-GATEP-Pad2)") (class "Default")
      (node (ref "OCP2") (pin "2") (pinfunction "GATEP_2") (pintype "bidirectional"))
    )
    (net (code "196") (name "unconnected-(OCP2-PWRGD-Pad5)") (class "Default")
      (node (ref "OCP2") (pin "5") (pinfunction "PWRGD_5") (pintype "bidirectional"))
    )
    (net (code "197") (name "unconnected-(R6-Pad1)") (class "Default")
      (node (ref "R6") (pin "1") (pinfunction "1_1") (pintype "passive"))
    )
    (net (code "198") (name "unconnected-(R7-Pad1)") (class "Default")
      (node (ref "R7") (pin "1") (pinfunction "1_1") (pintype "passive"))
    )
    (net (code "199") (name "unconnected-(R29-Pad1)") (class "Default")
      (node (ref "R29") (pin "1") (pinfunction "1_1") (pintype "passive"))
    )
    (net (code "200") (name "unconnected-(SFD1-PadC)") (class "Default")
      (node (ref "SFD1") (pin "C") (pinfunction "C_C") (pintype "passive"))
    )
    (net (code "201") (name "unconnected-(TRX1-NC1-PadP$4)") (class "Default")
      (node (ref "TRX1") (pin "P$4") (pinfunction "NC1_P$4") (pintype "bidirectional"))
    )
    (net (code "202") (name "unconnected-(TRX1-NC2-PadP$5)") (class "Default")
      (node (ref "TRX1") (pin "P$5") (pinfunction "NC2_P$5") (pintype "bidirectional"))
    )
    (net (code "203") (name "unconnected-(TRX1-NC3-PadP$6)") (class "Default")
      (node (ref "TRX1") (pin "P$6") (pinfunction "NC3_P$6") (pintype "bidirectional"))
    )
    (net (code "204") (name "unconnected-(TRX1-NC4-PadP$7)") (class "Default")
      (node (ref "TRX1") (pin "P$7") (pinfunction "NC4_P$7") (pintype "bidirectional"))
    )
    (net (code "205") (name "unconnected-(TRX1-NC5-PadP$8)") (class "Default")
      (node (ref "TRX1") (pin "P$8") (pinfunction "NC5_P$8") (pintype "bidirectional"))
    )
    (net (code "206") (name "unconnected-(TRX2-SQ-Pad1)") (class "Default")
      (node (ref "TRX2") (pin "1") (pinfunction "SQ_1") (pintype "output"))
    )
  )
)
